# soap-disp-20210518.net
KiCad netlist of a schematic drawn in EasyEDA
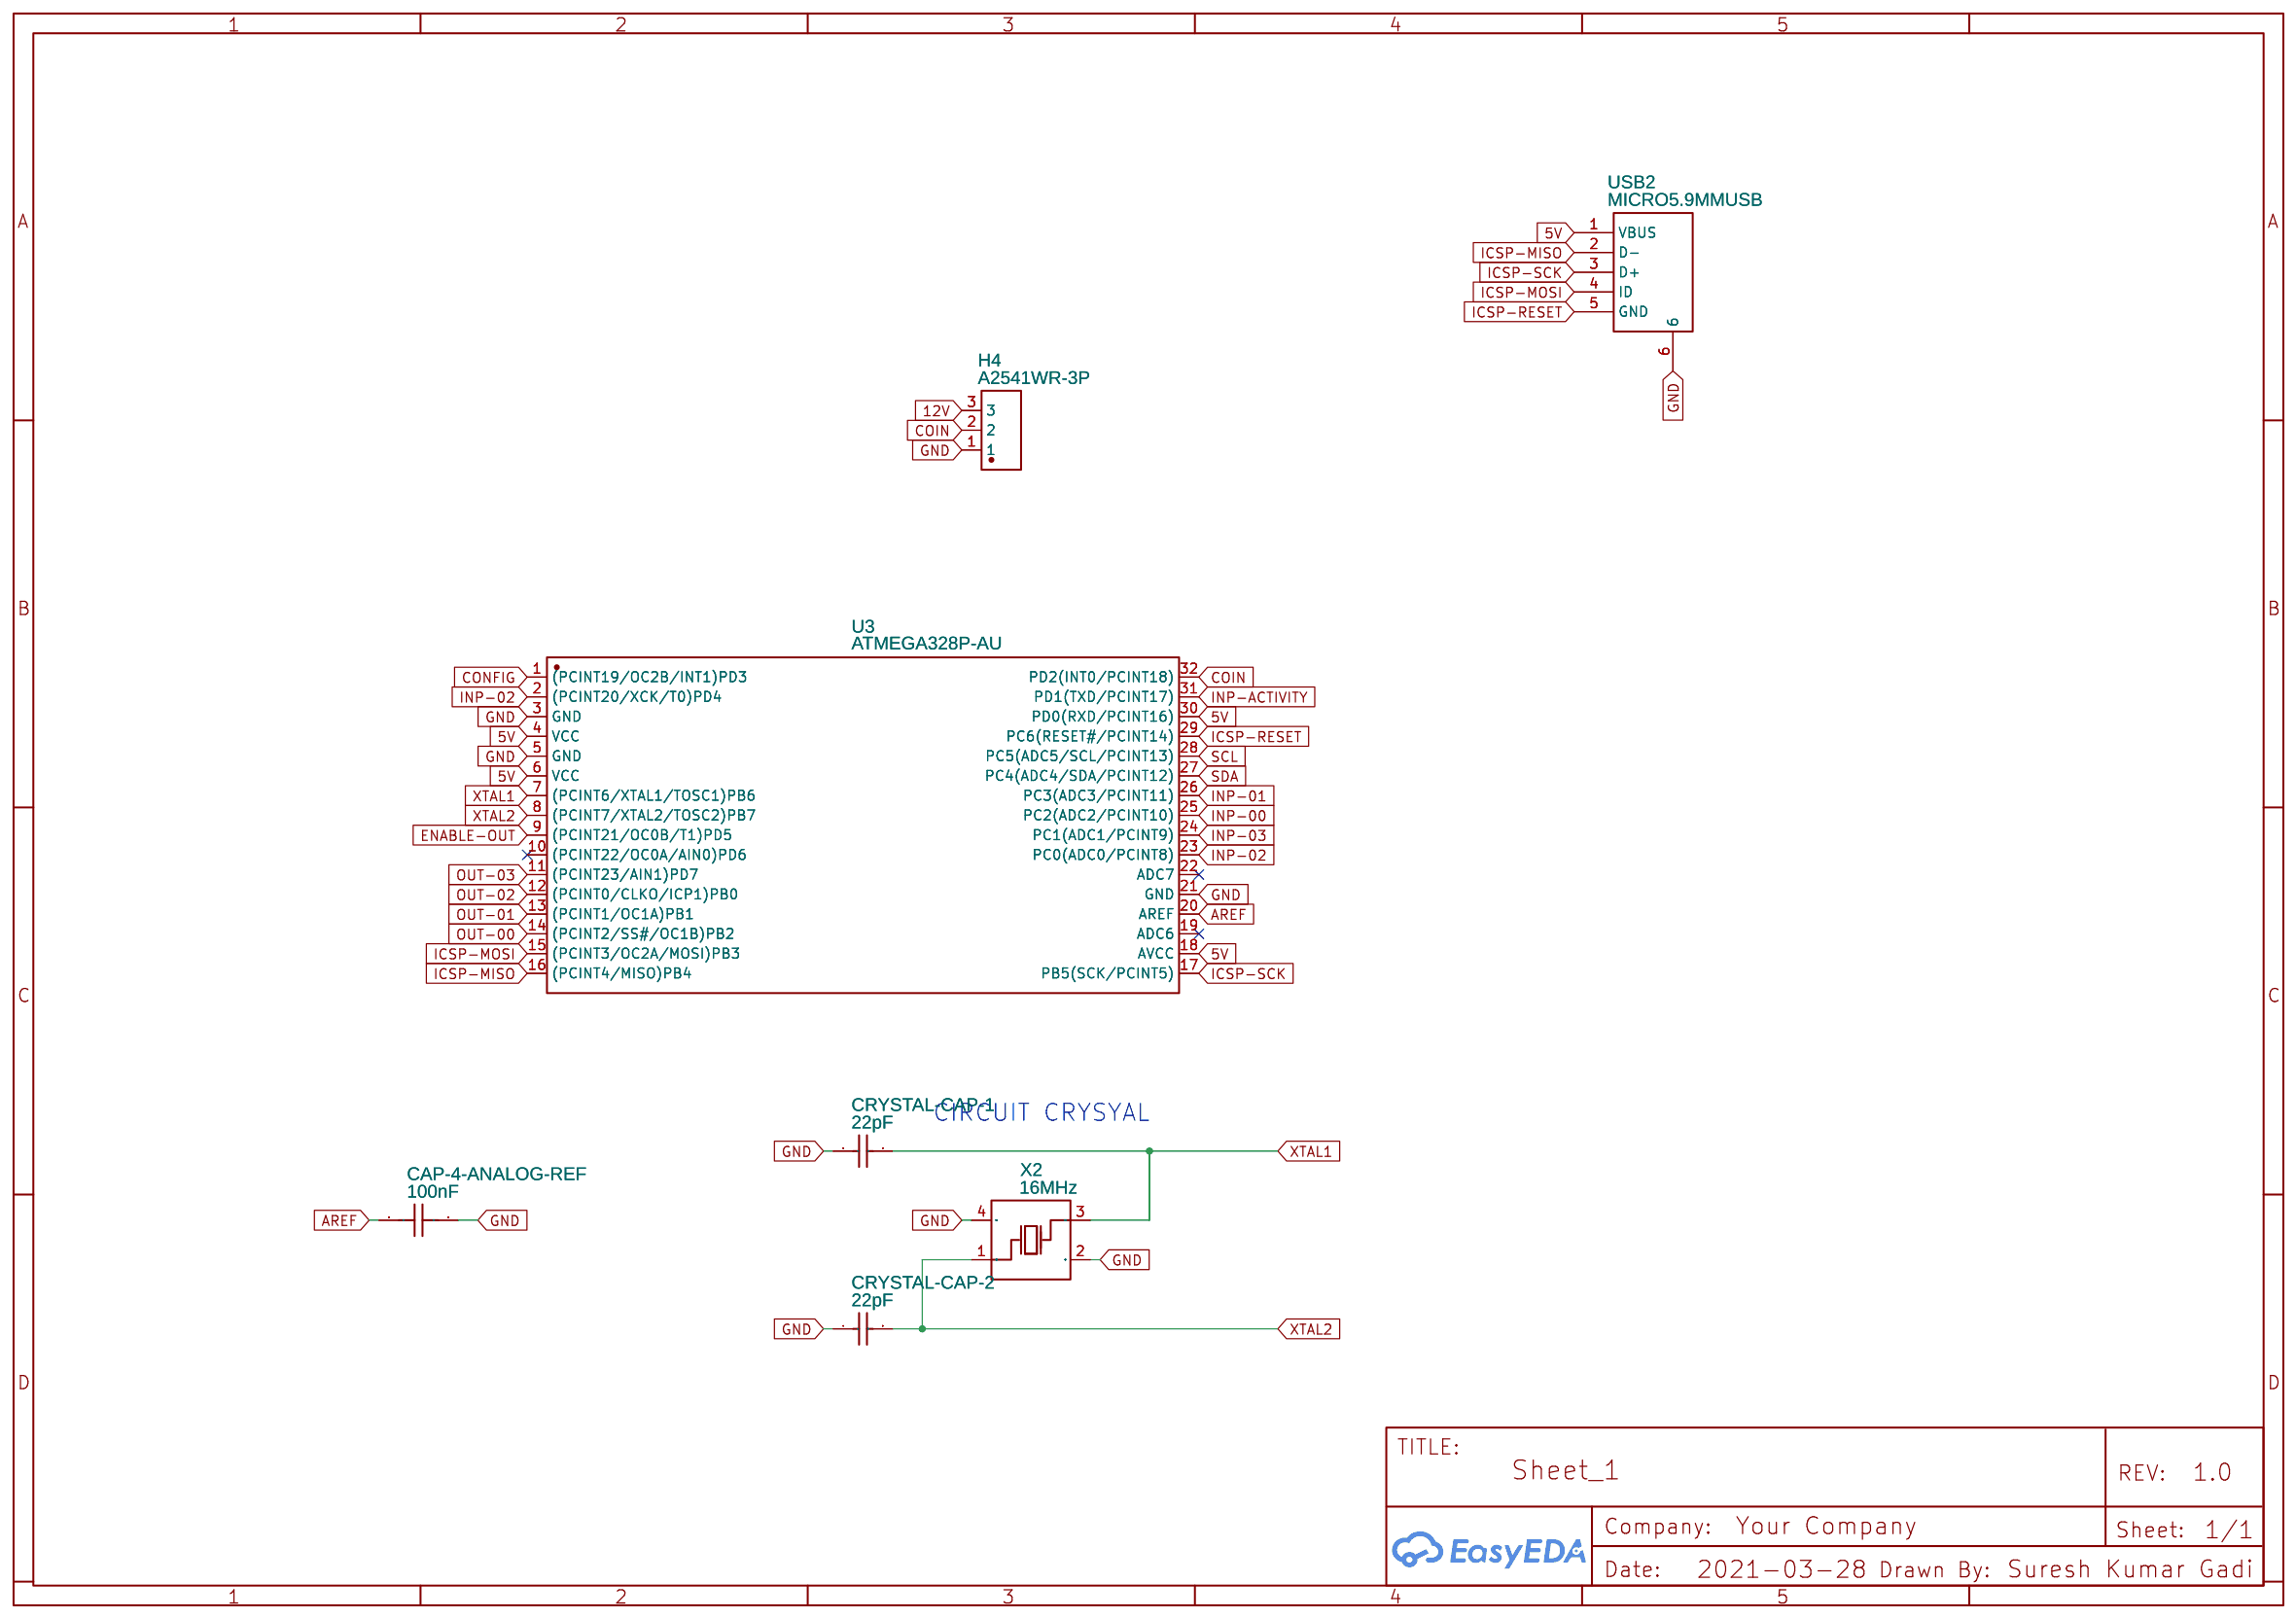
[diagram p0: Computer]
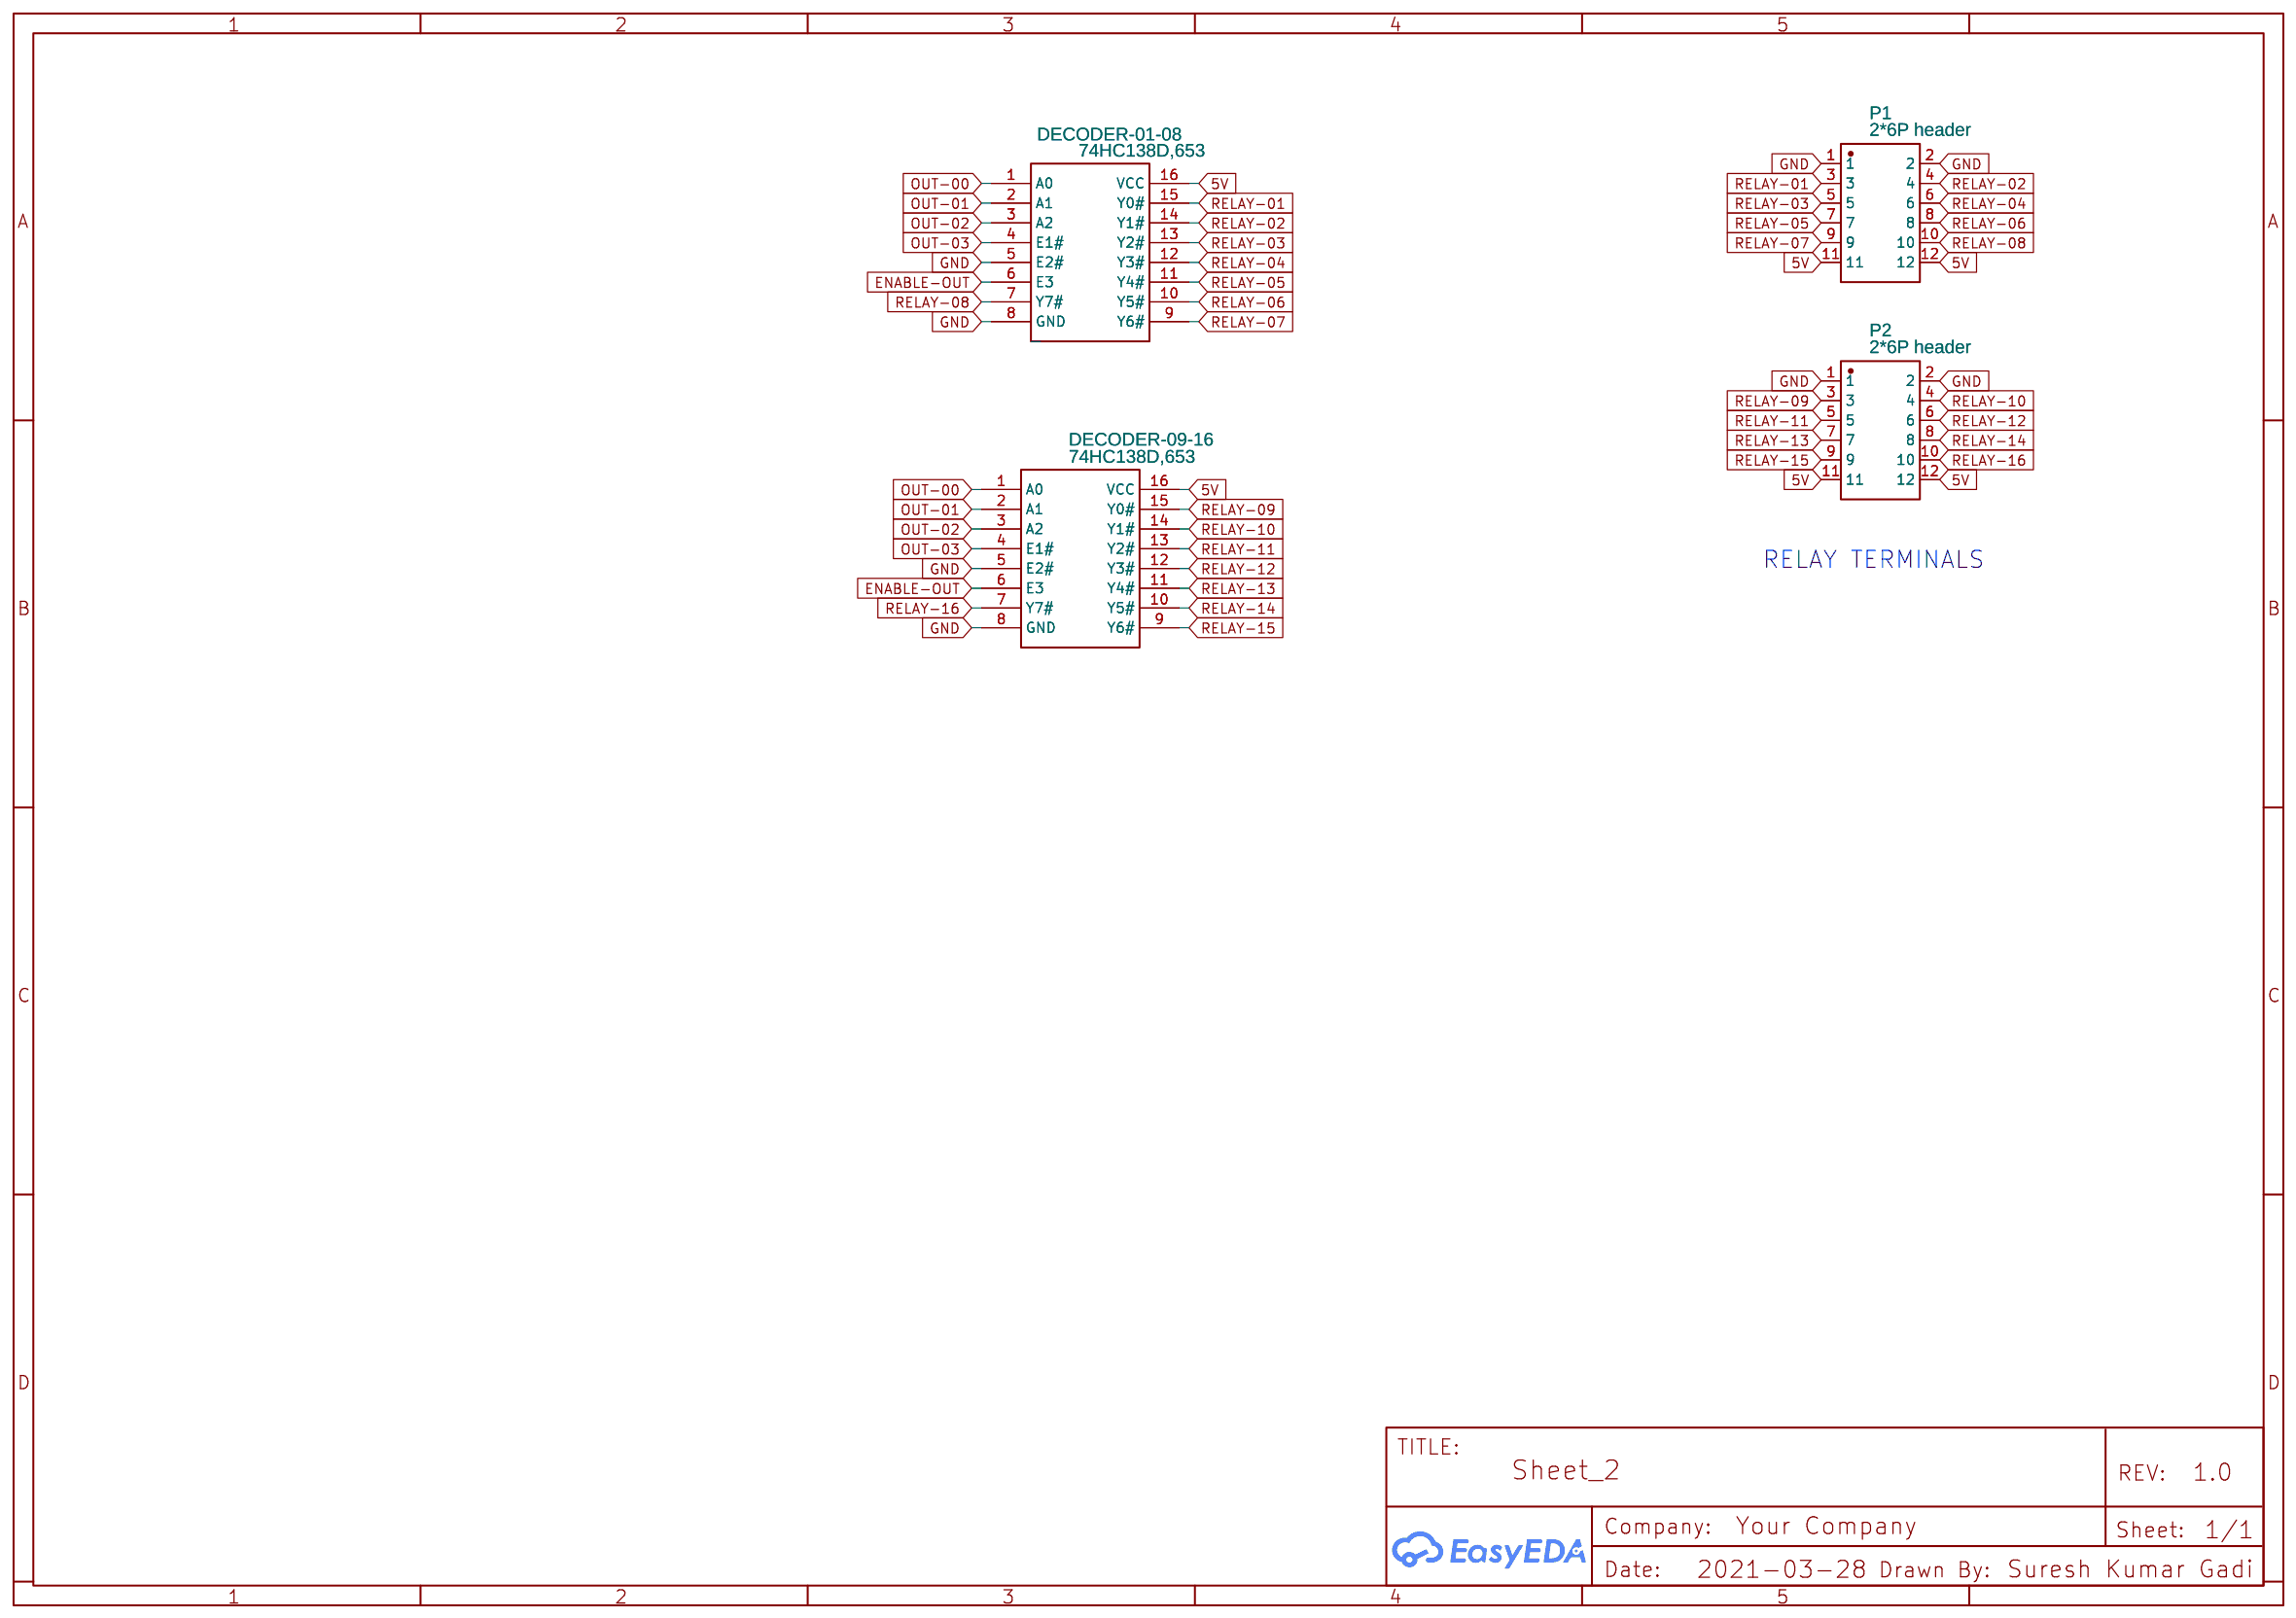
[diagram p1: Relays]
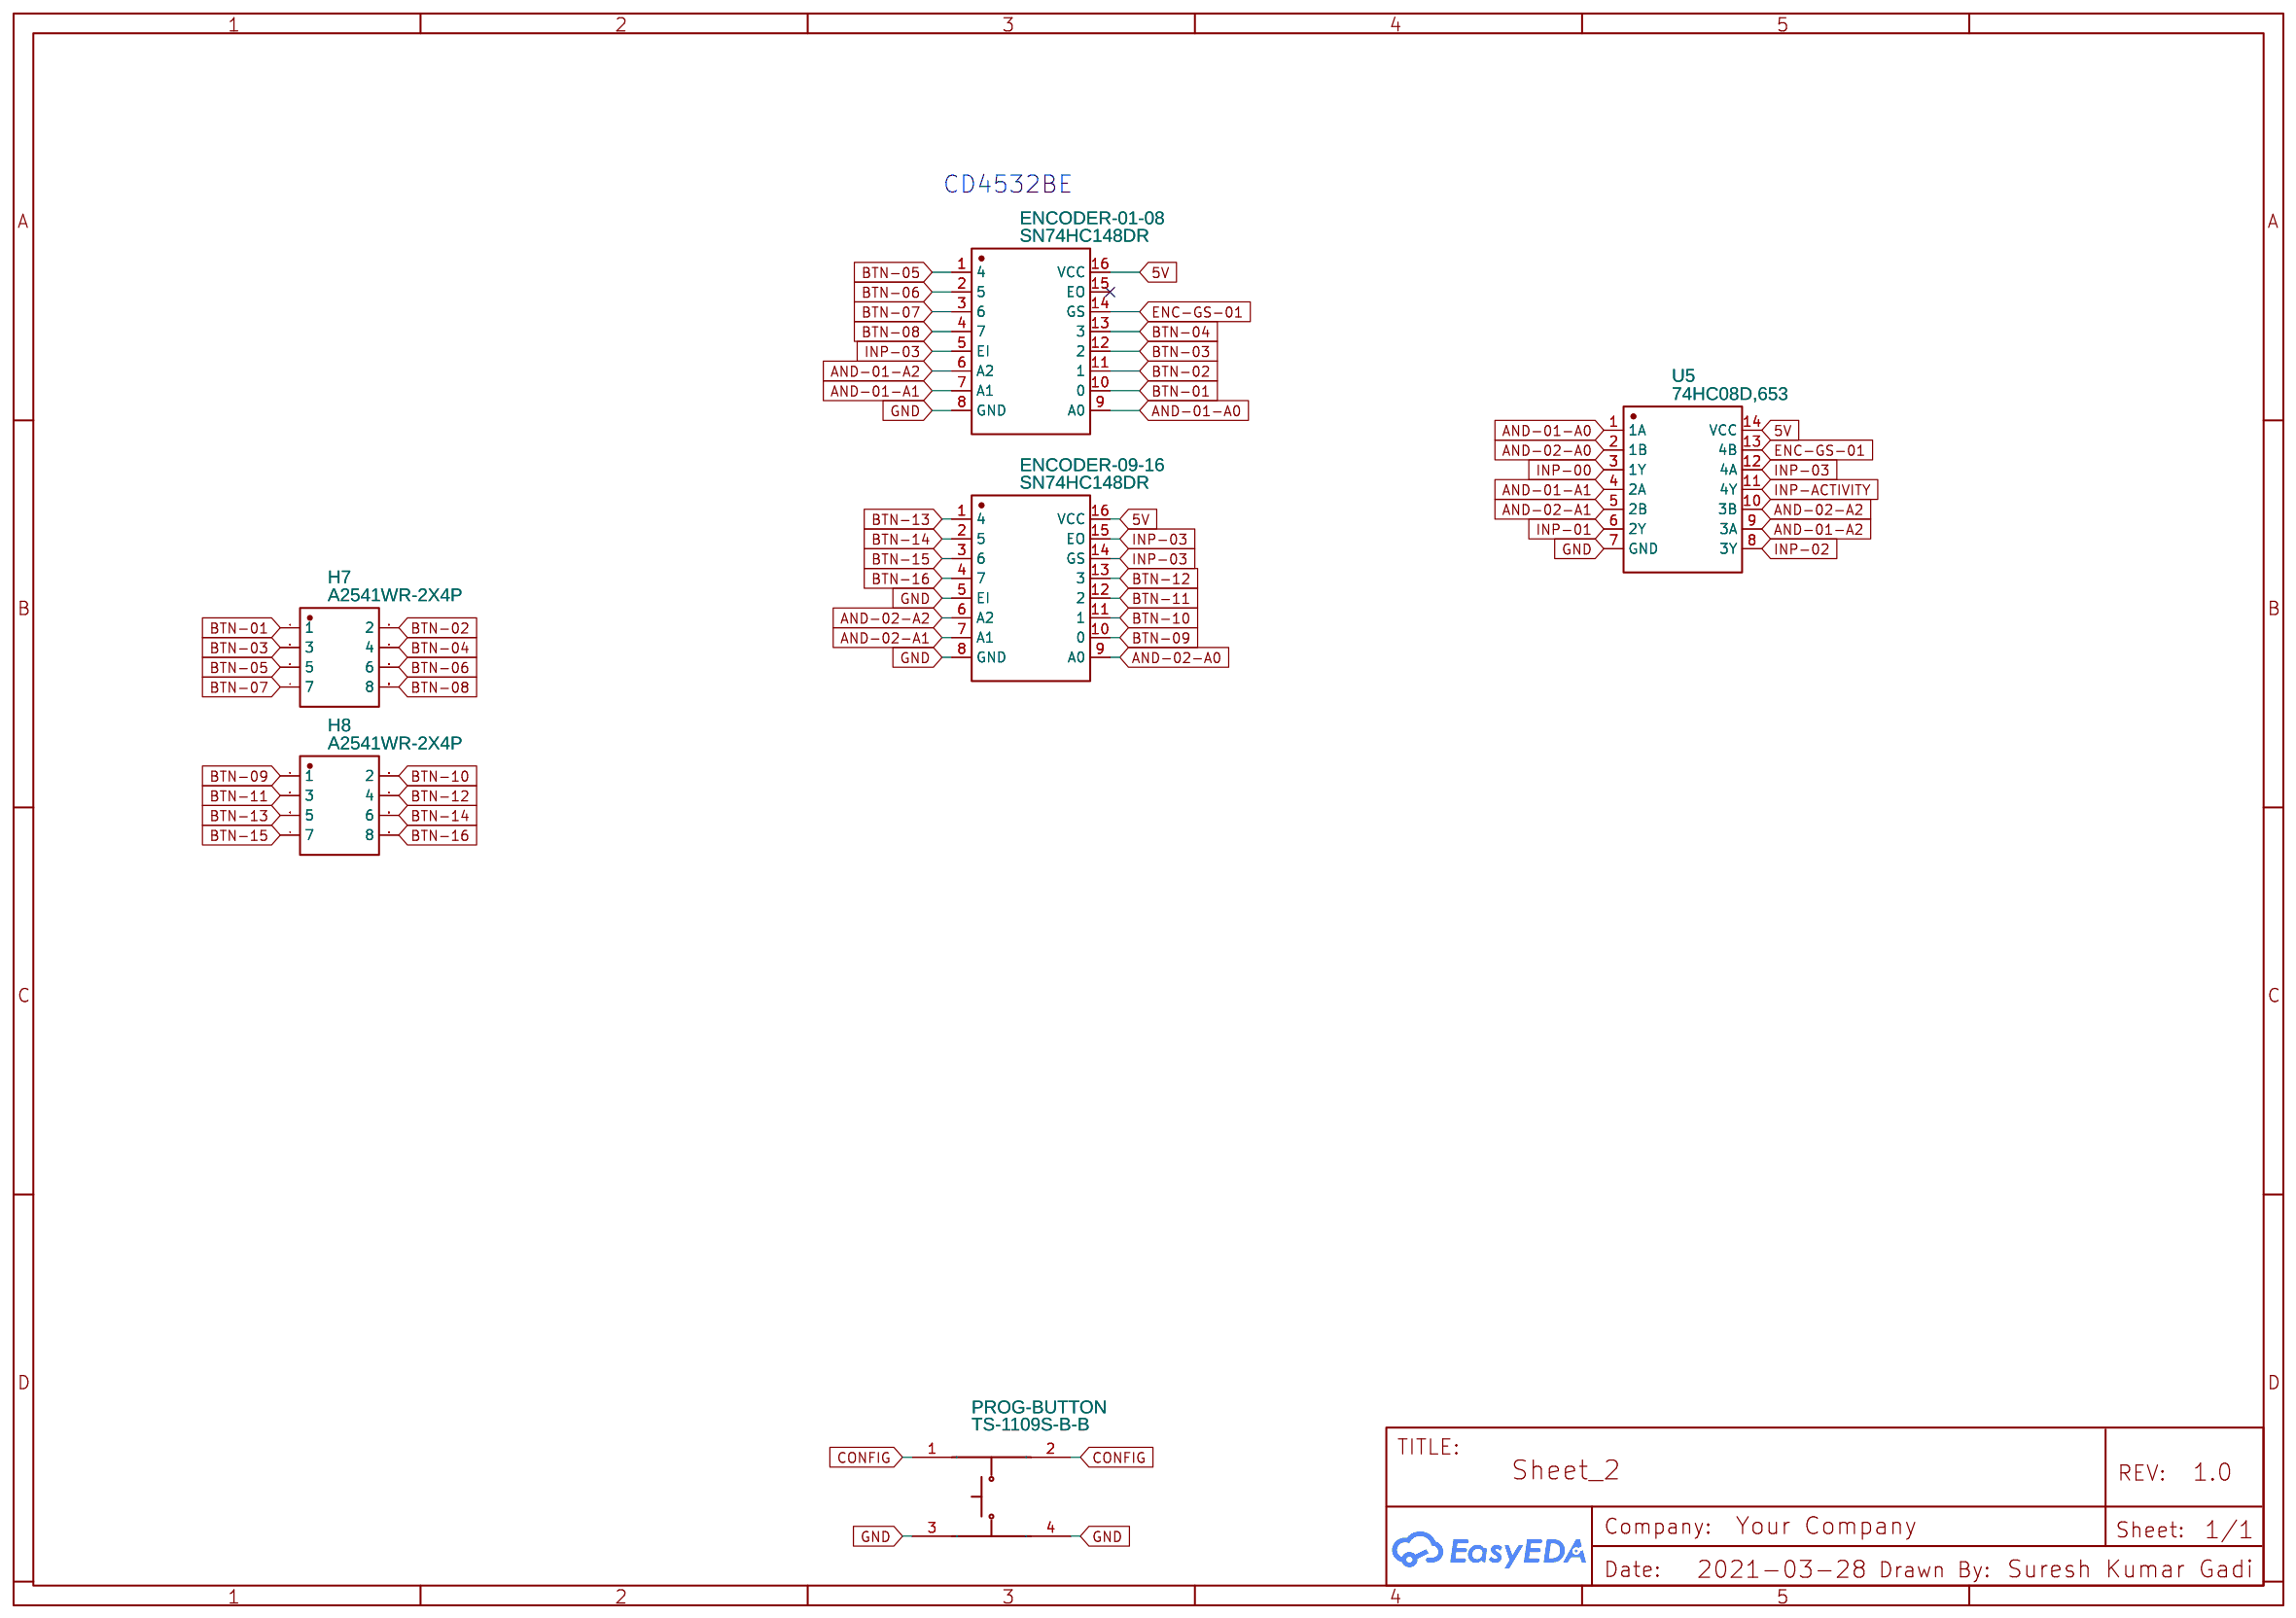
[diagram p2: Buttons]
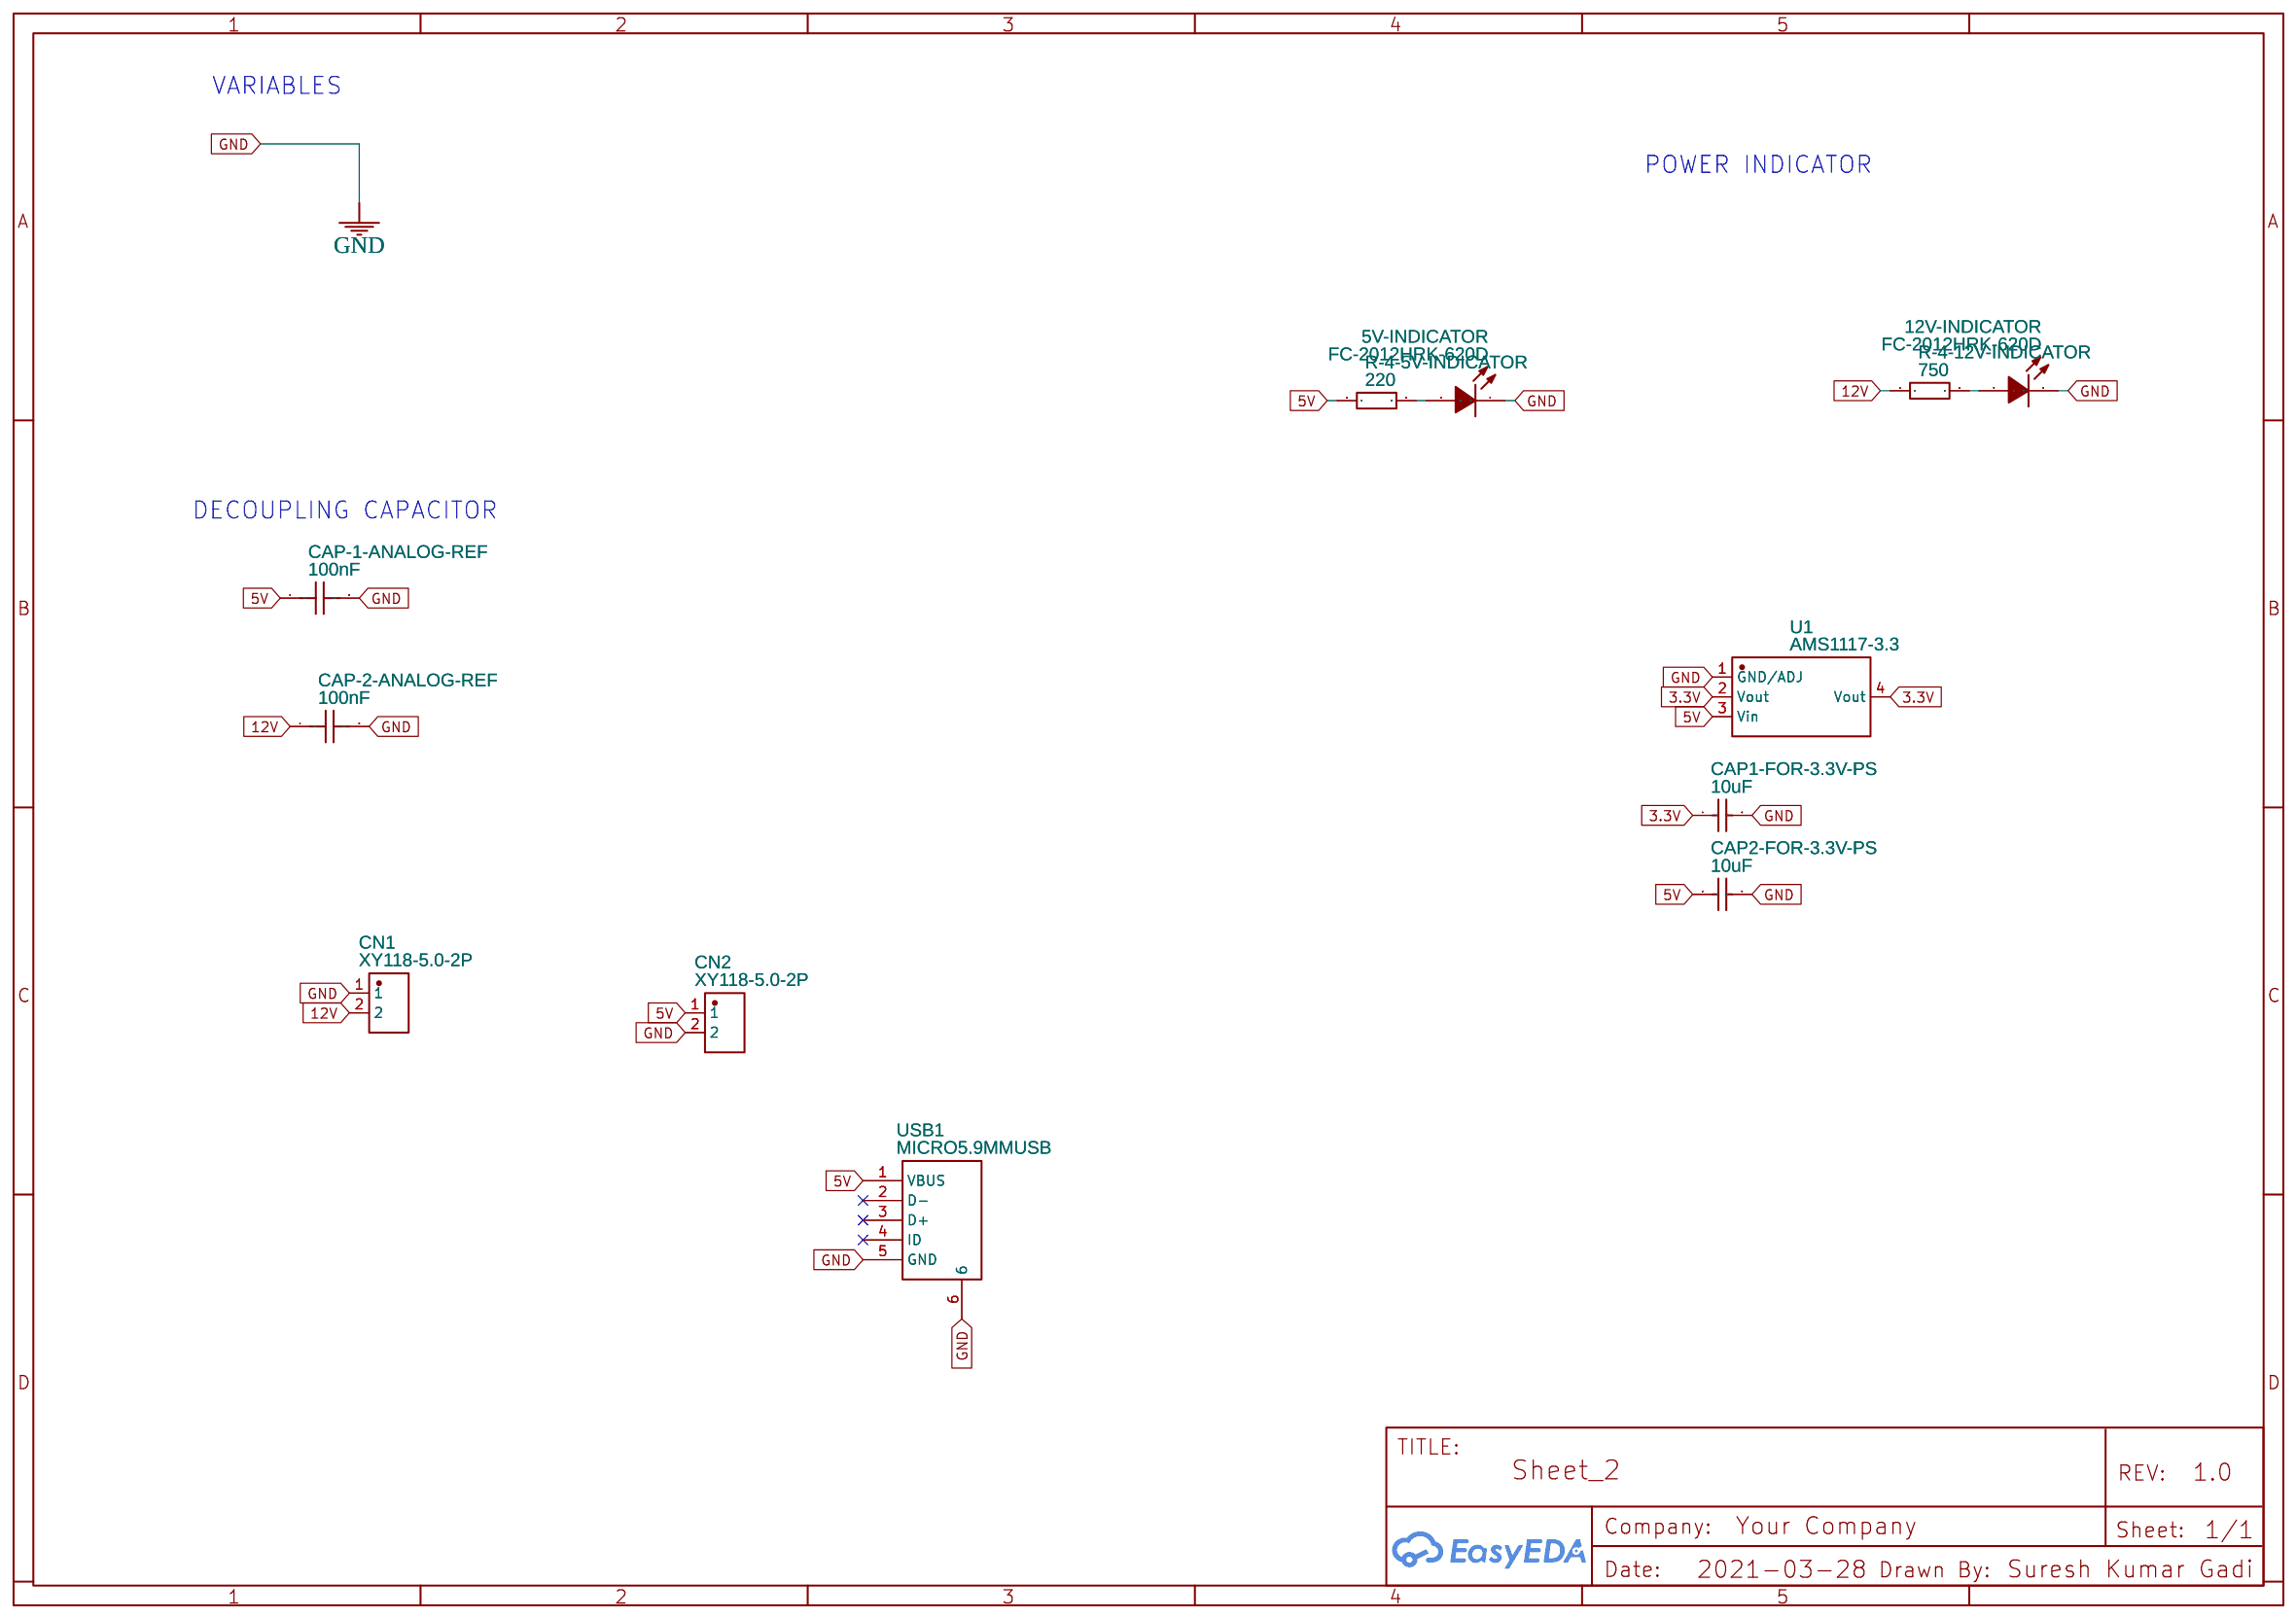
[diagram p3: Power]
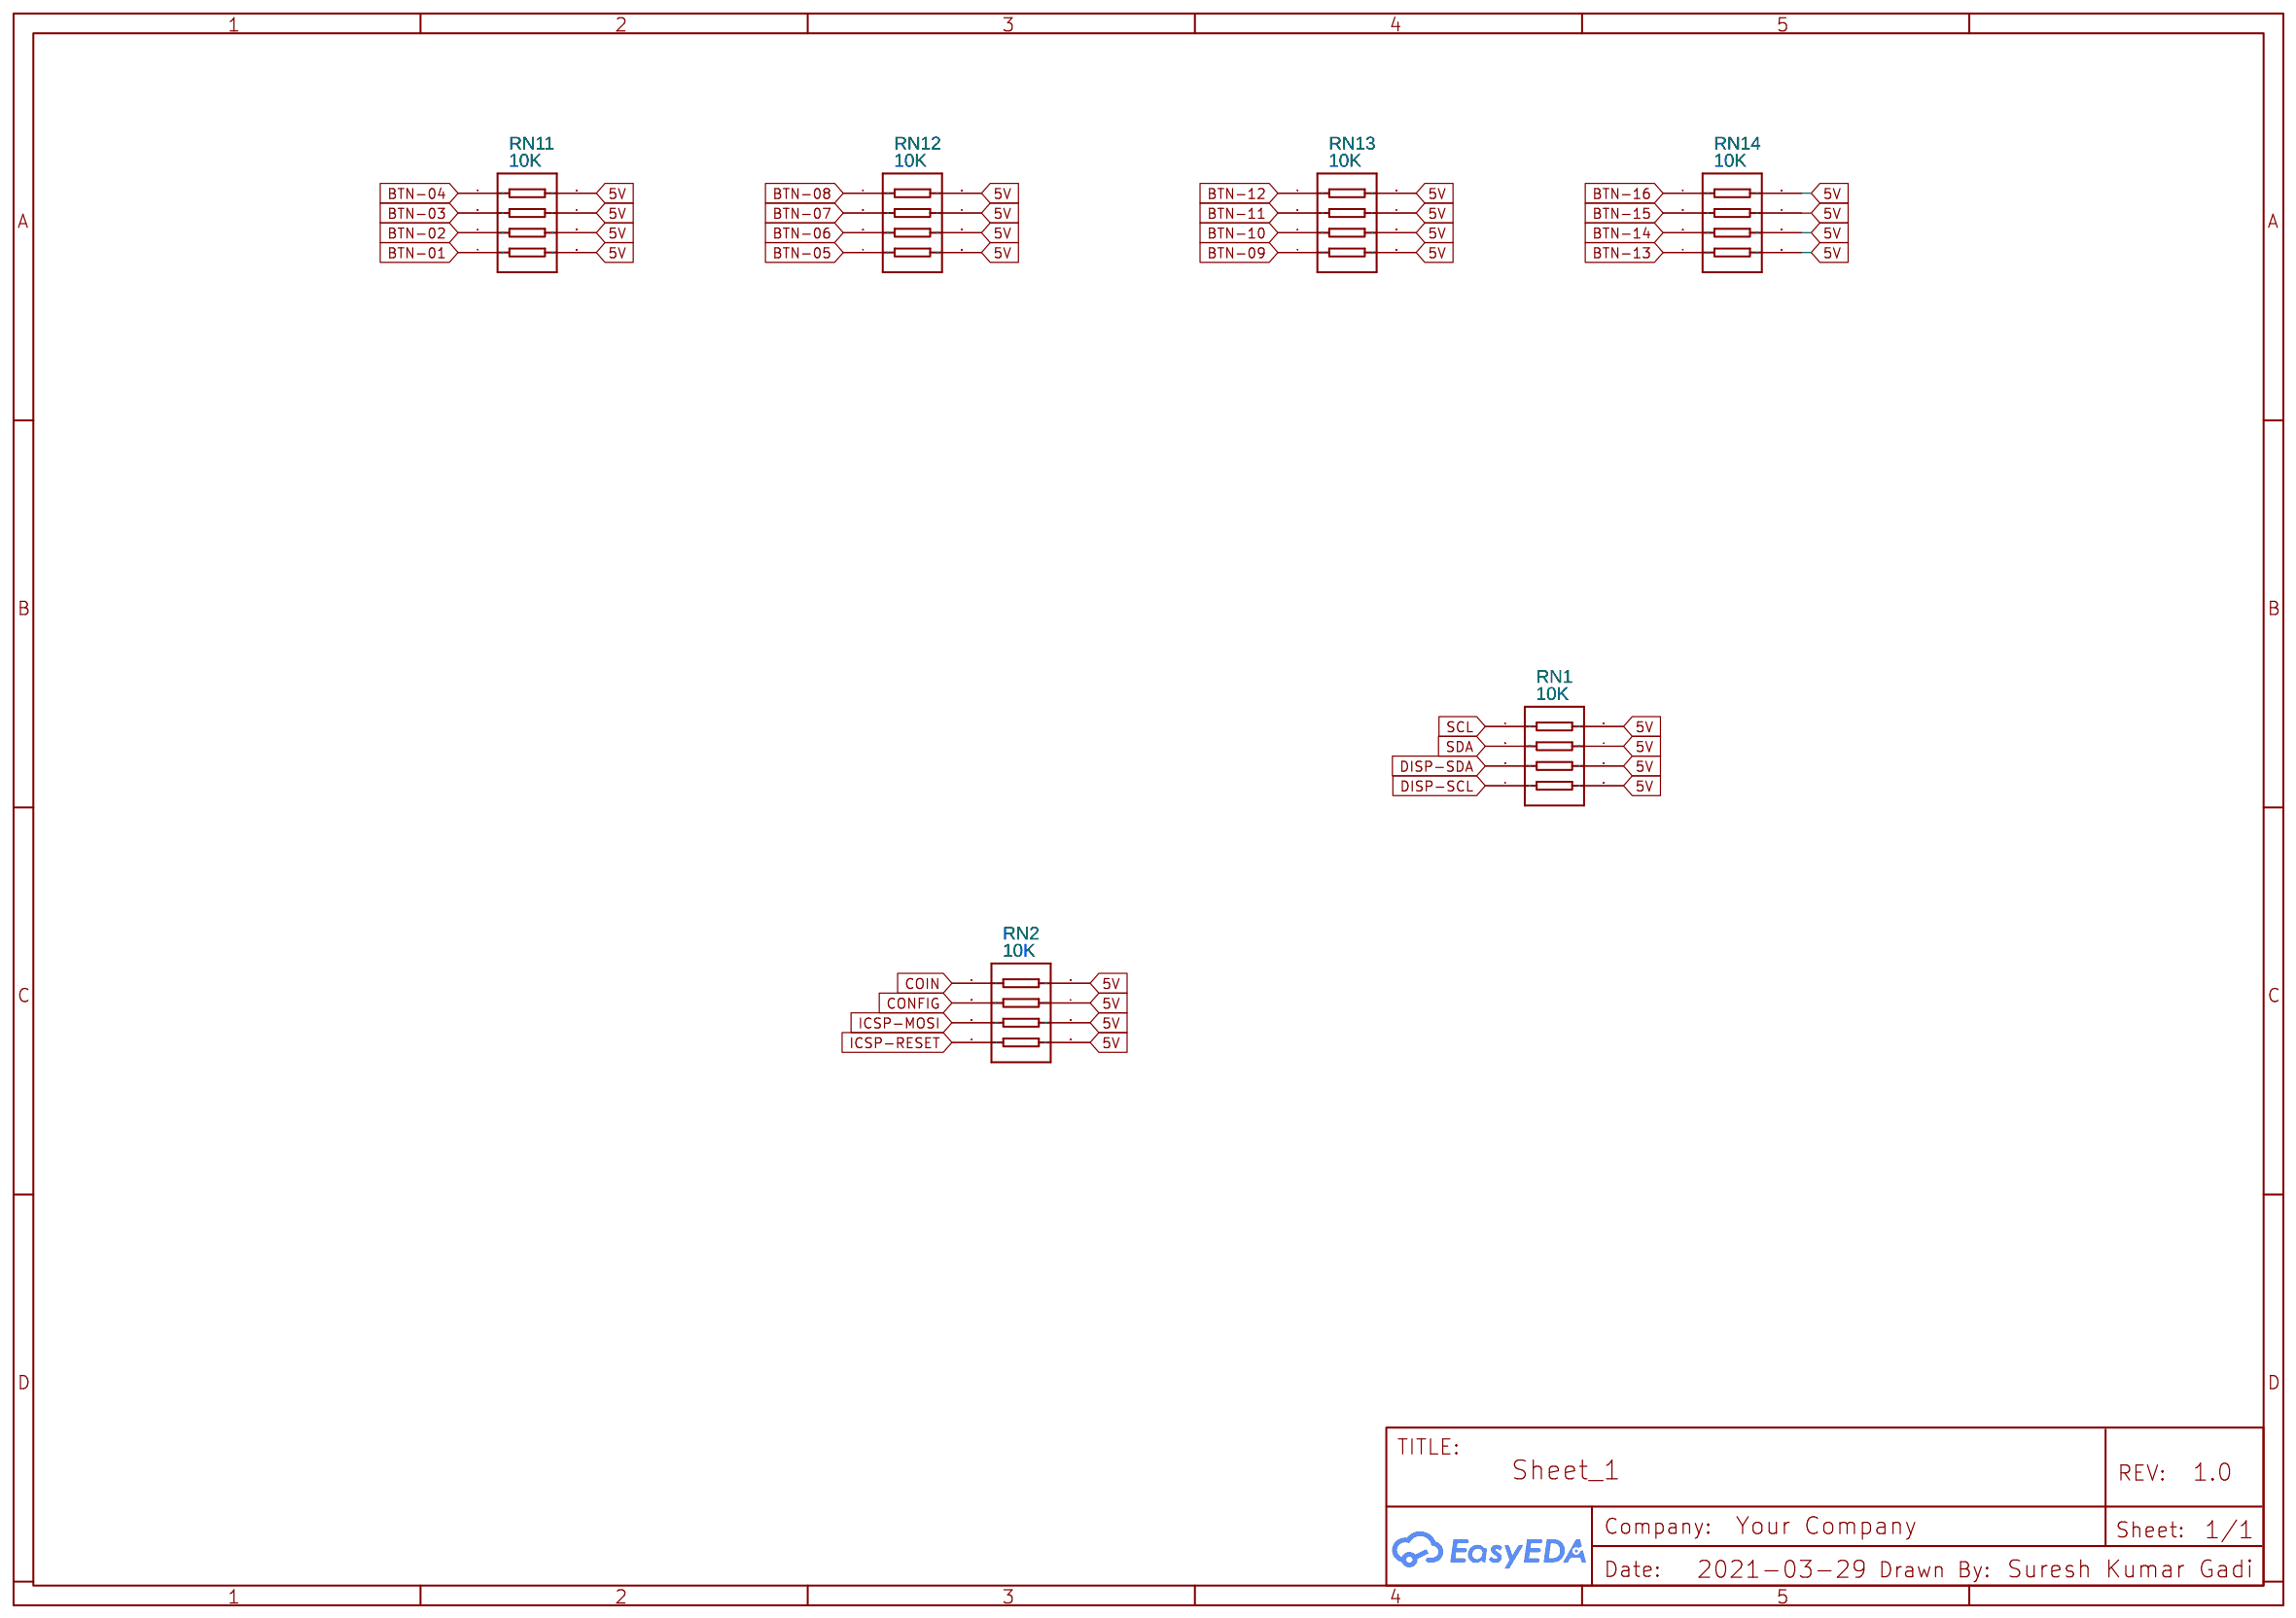
[diagram p4: Pull up-down]
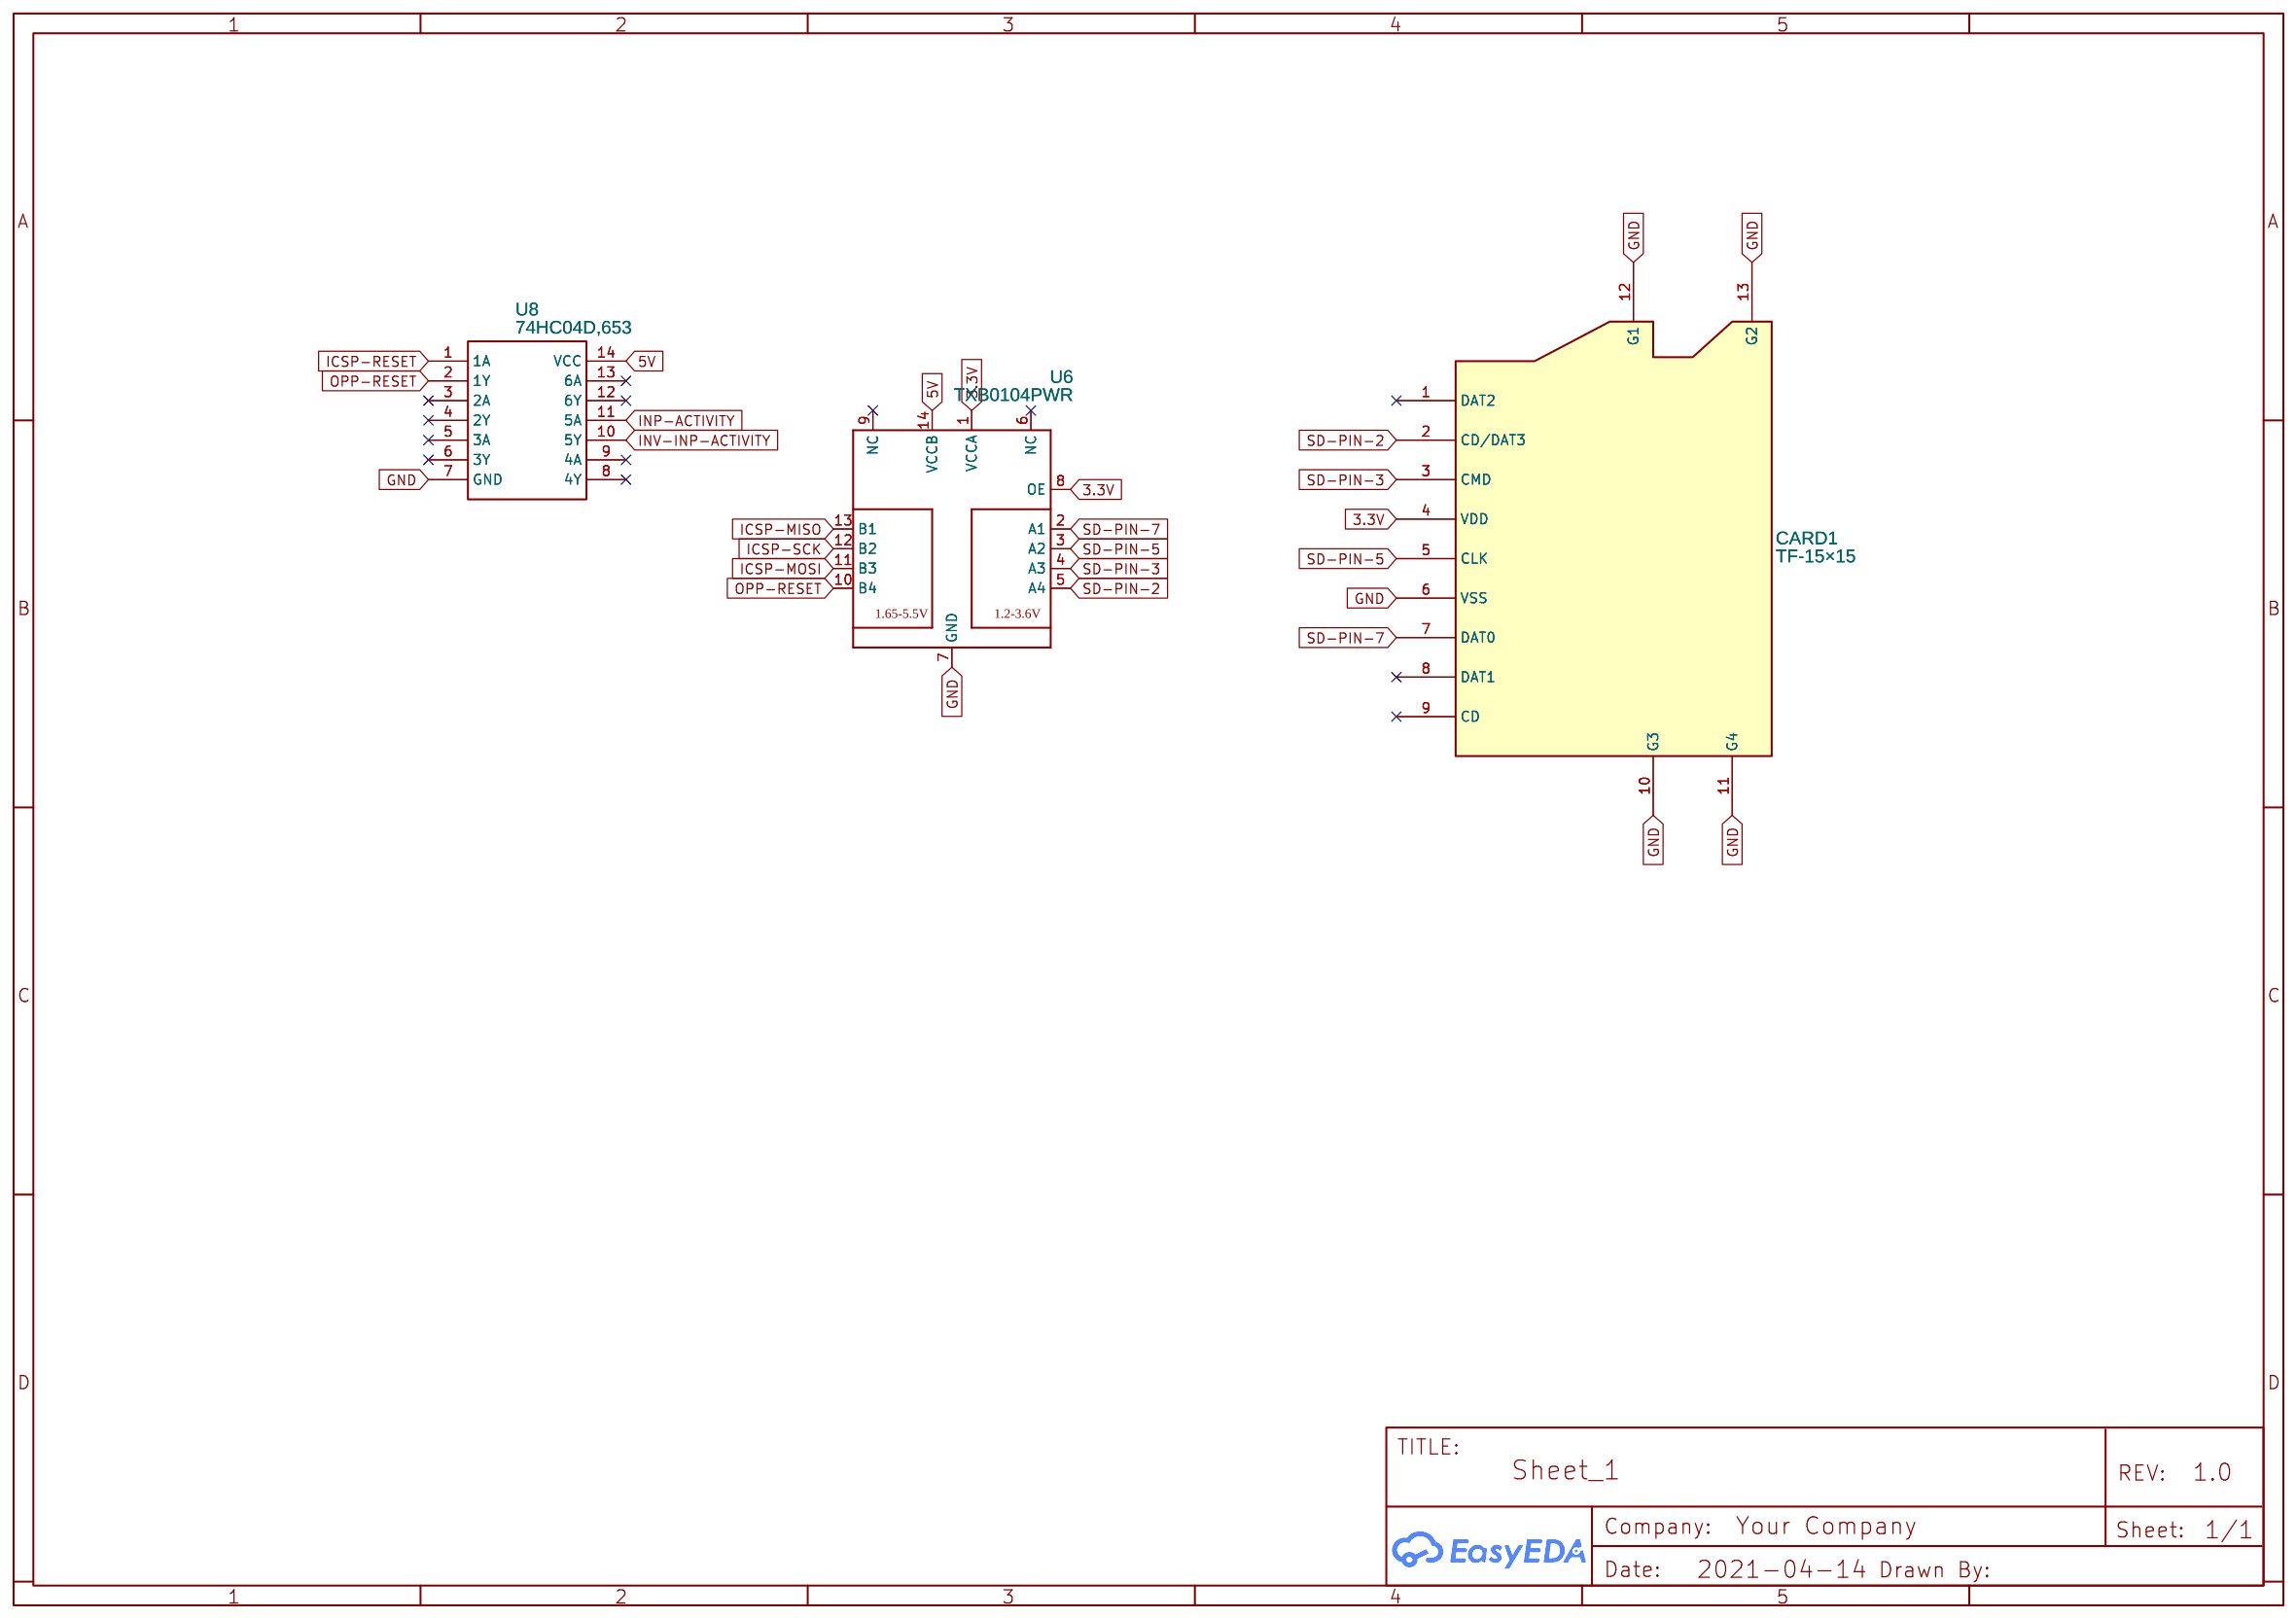
[diagram p5: SD Card]
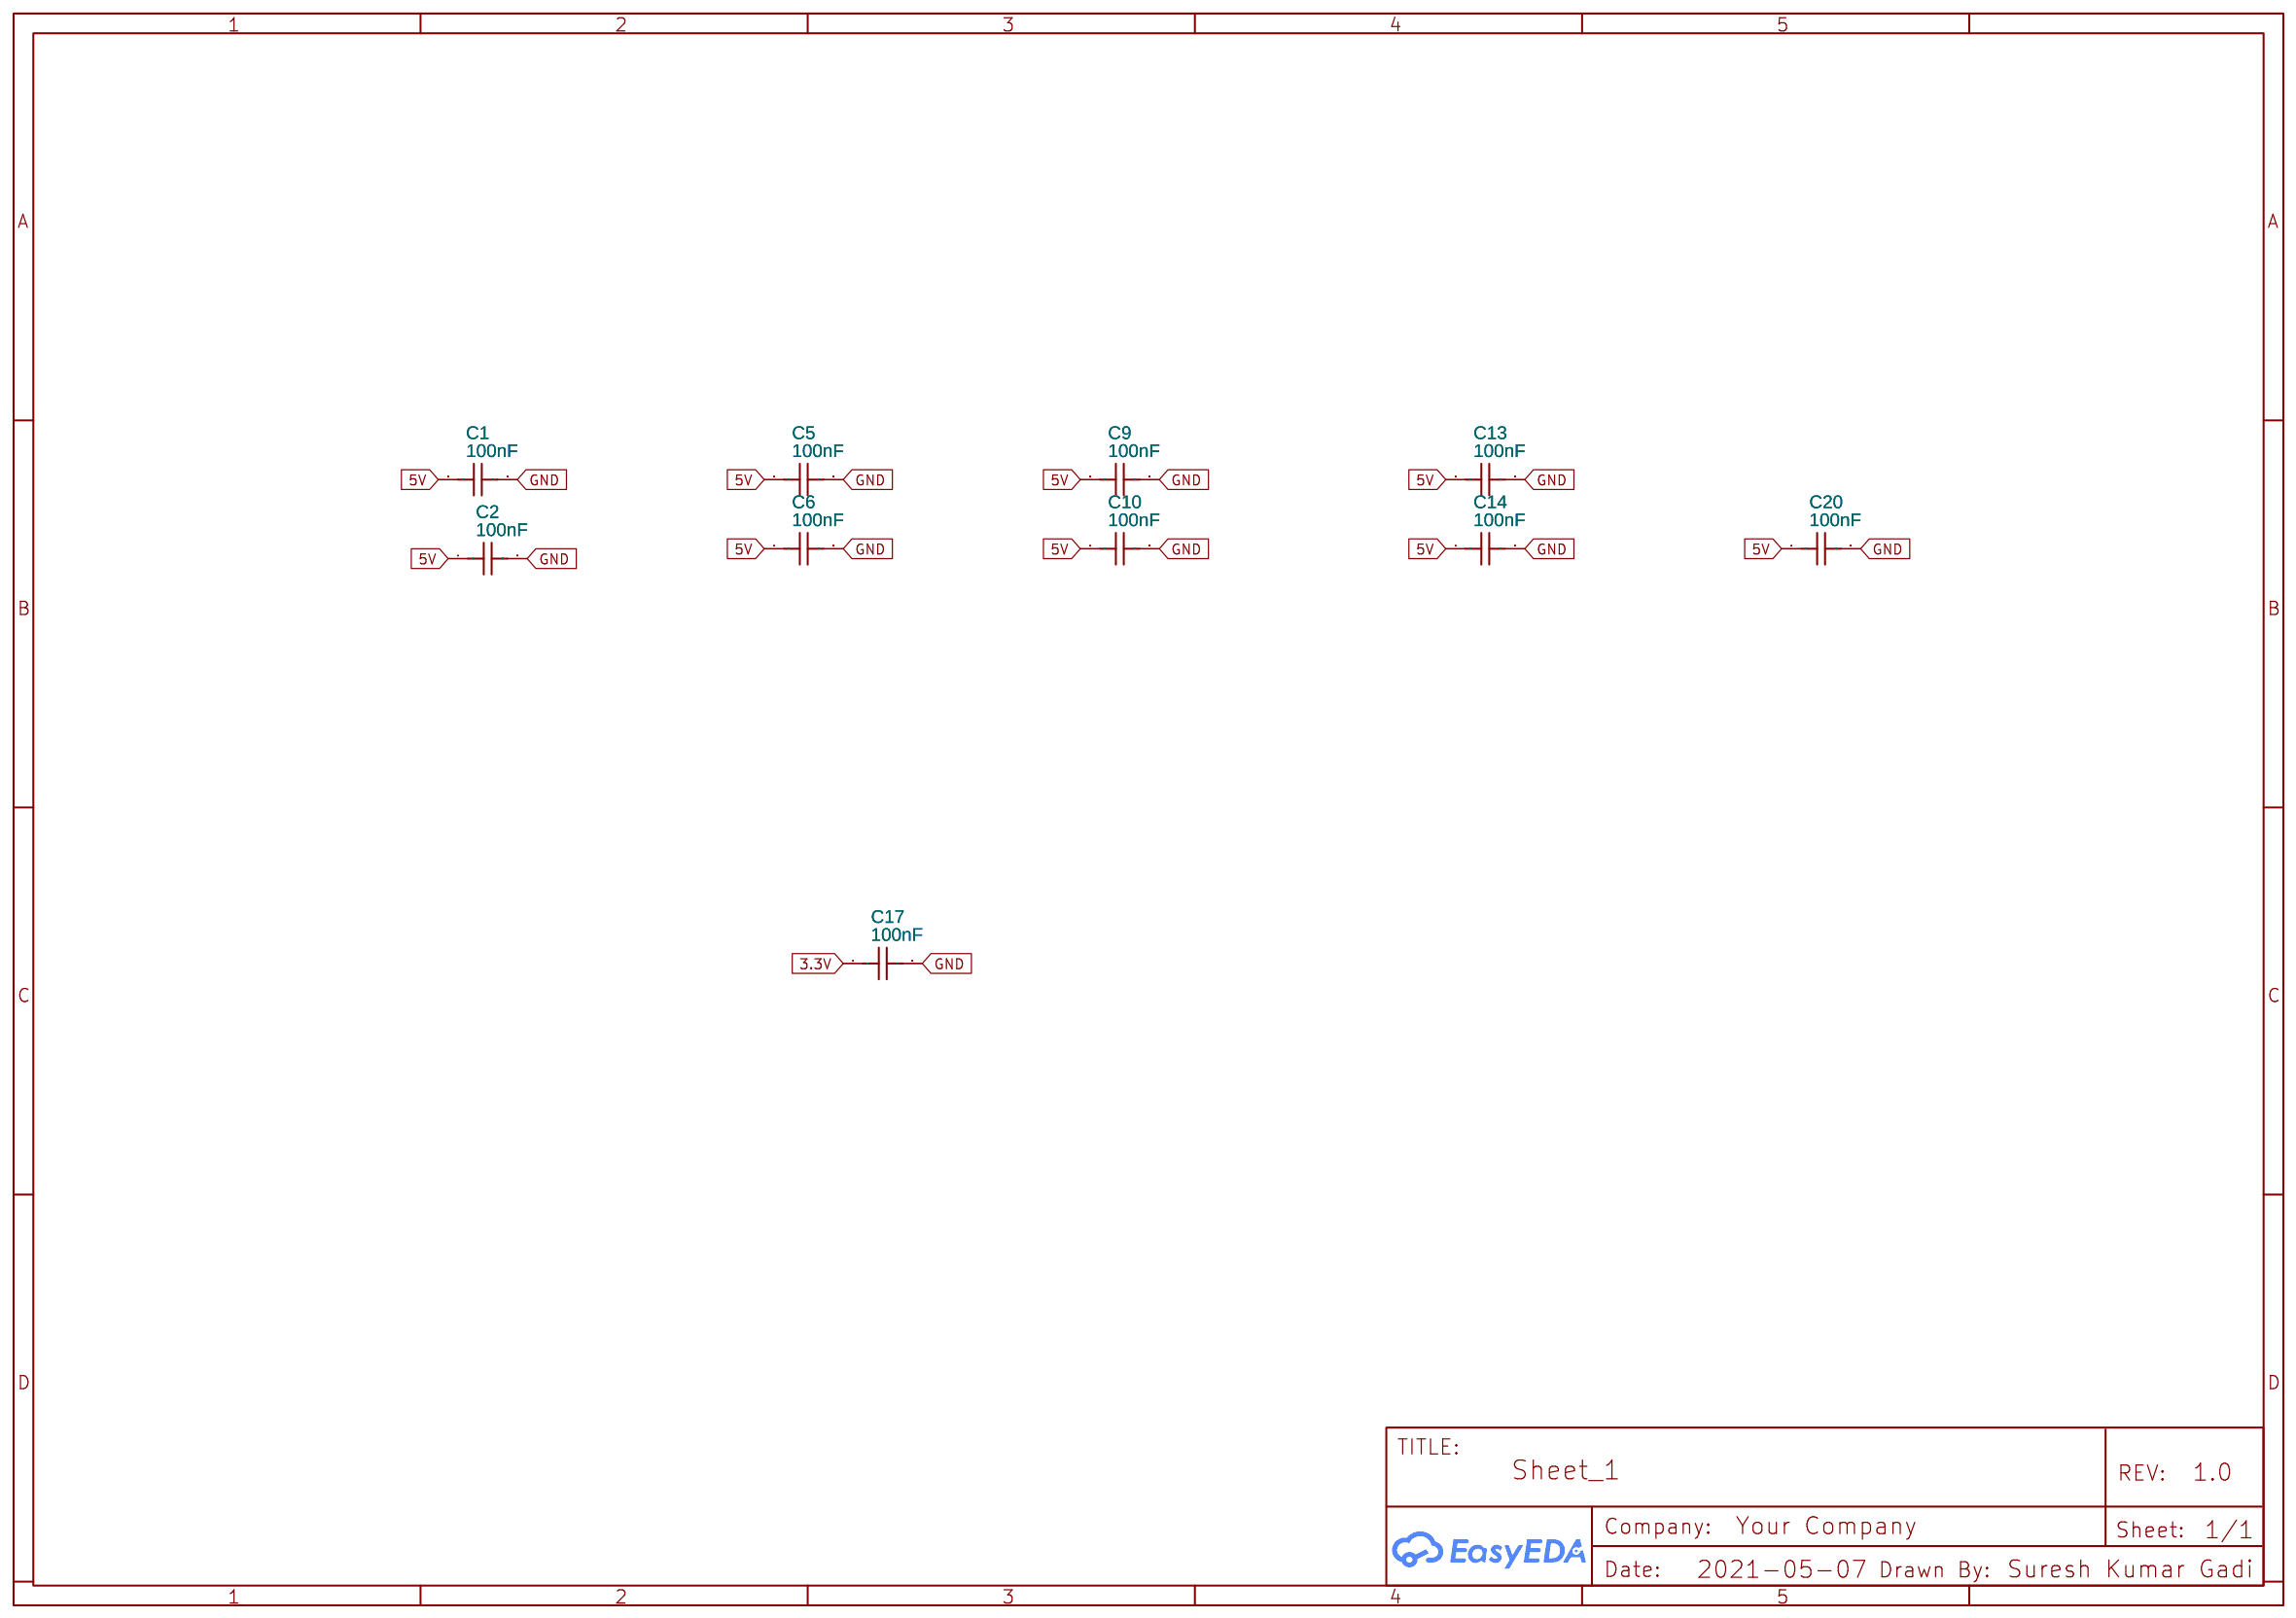
[diagram p6: Capacitor]
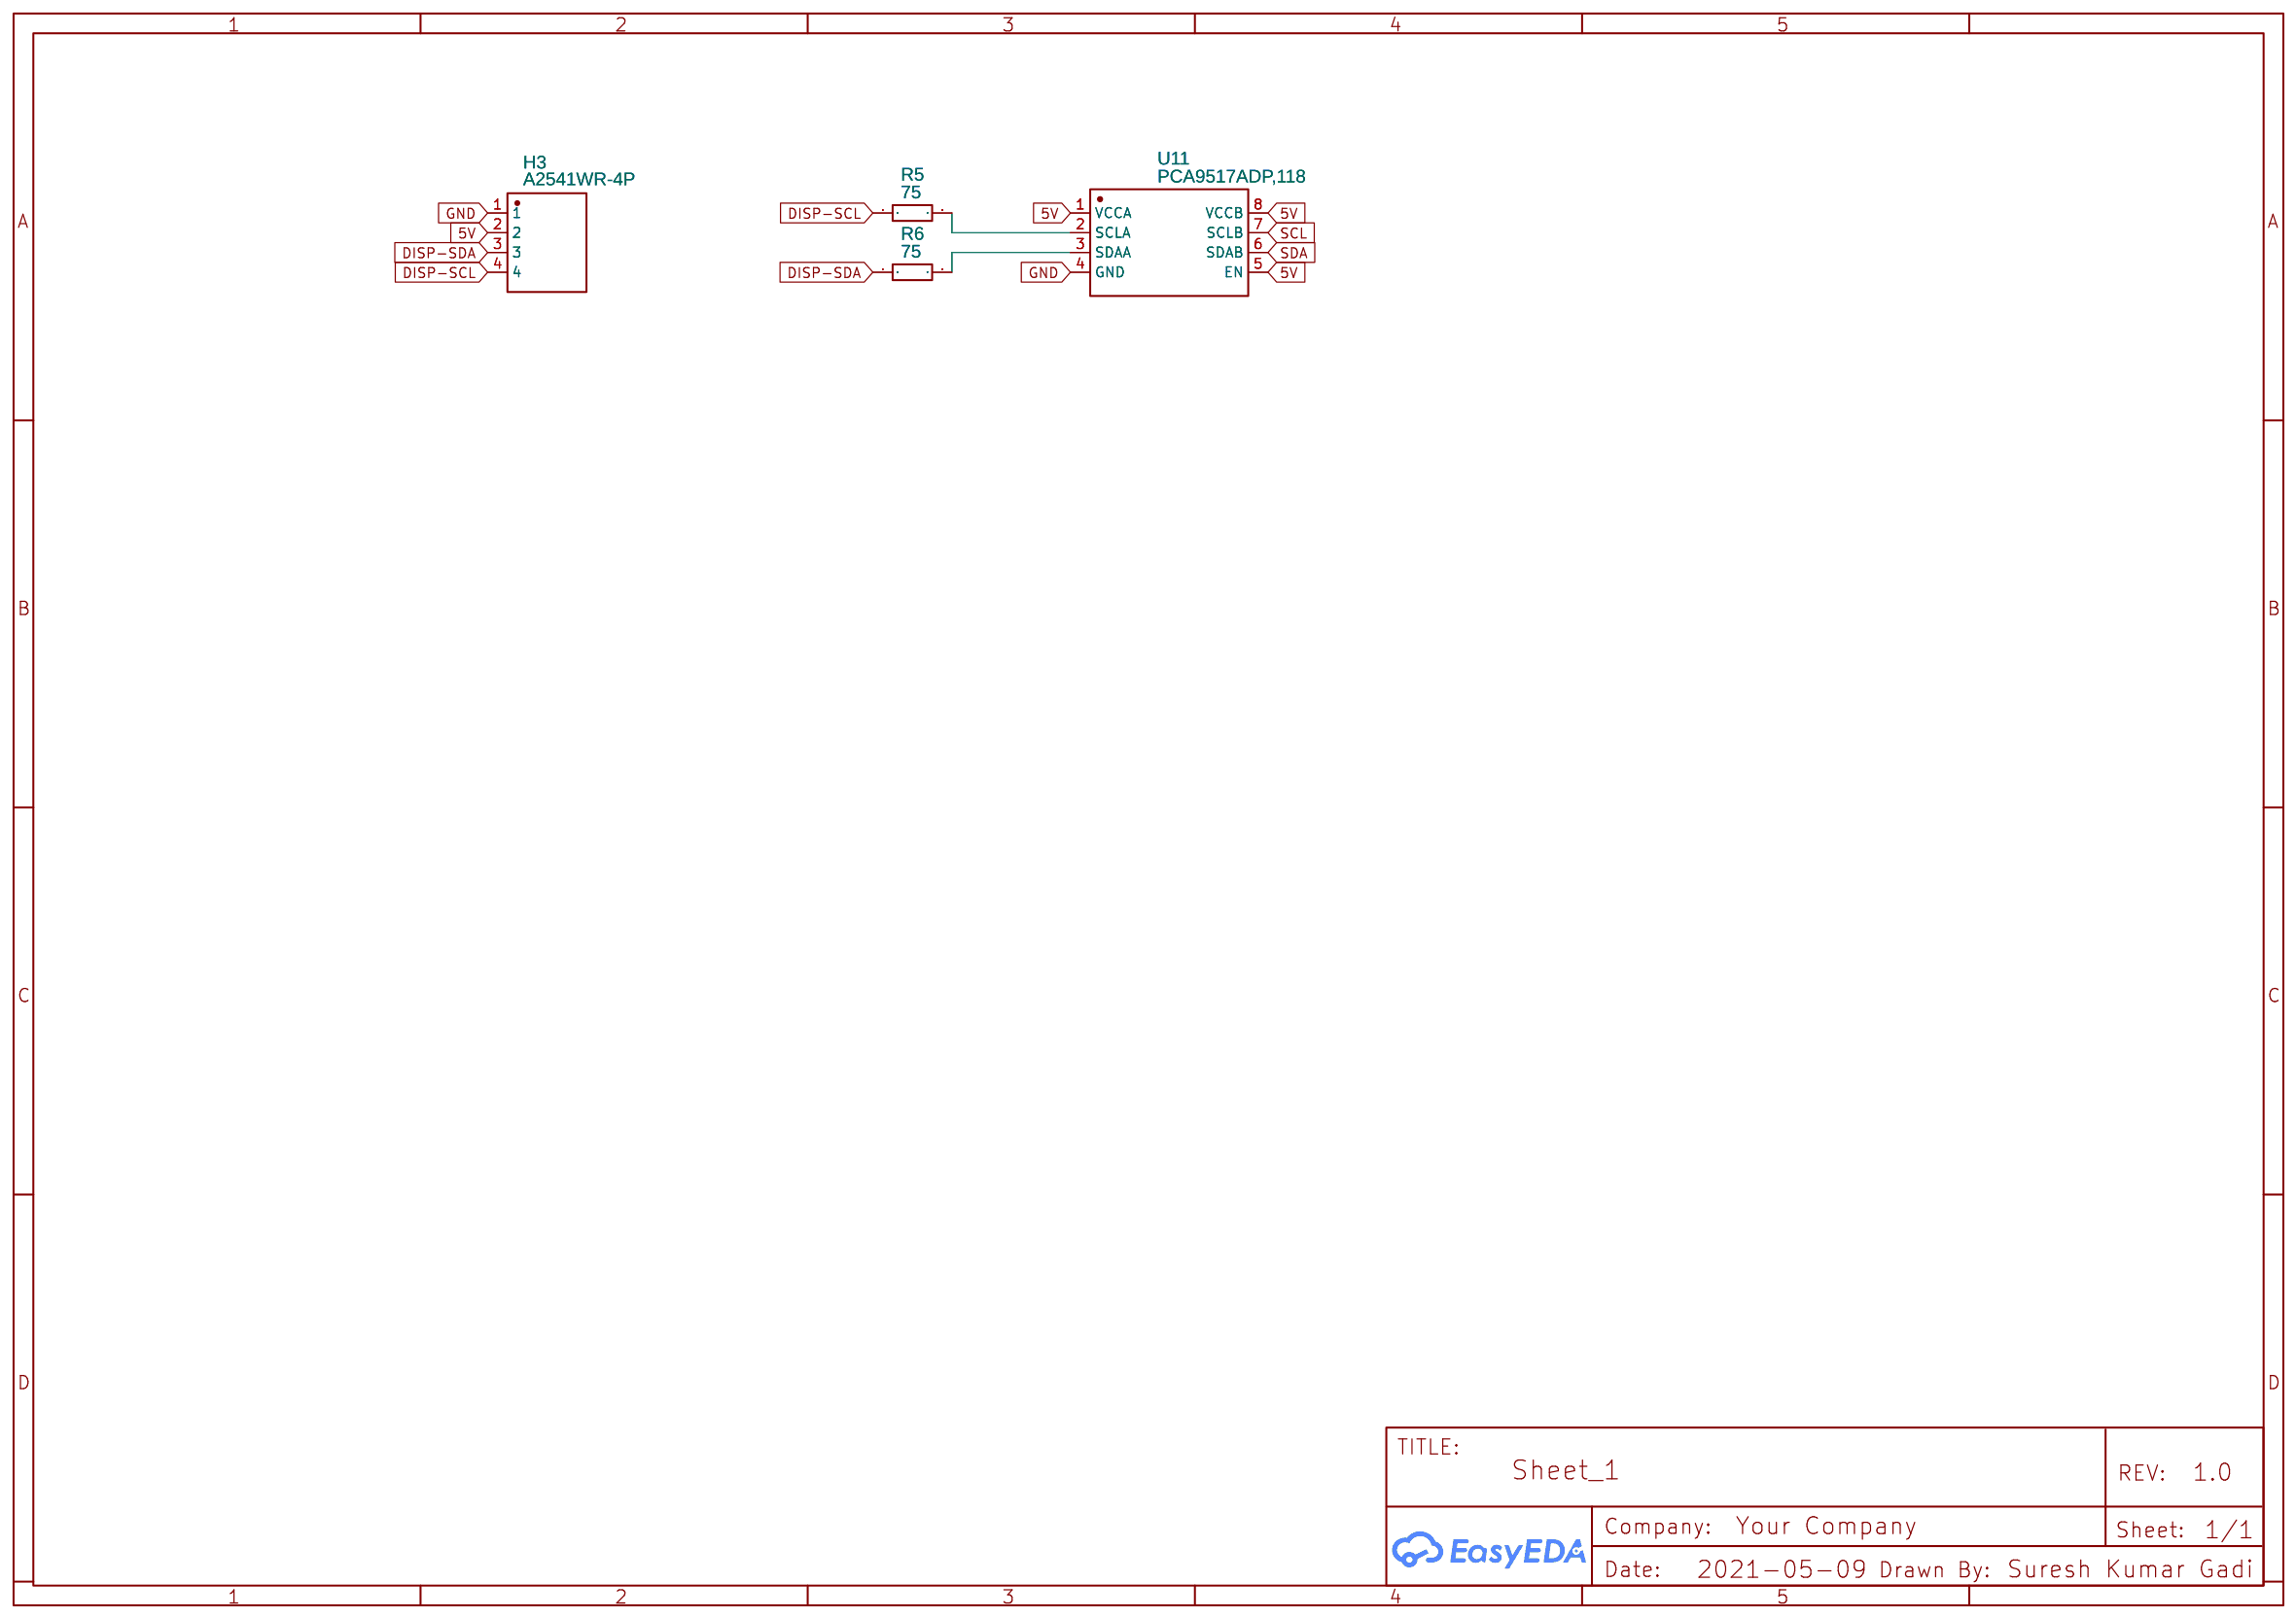
[diagram p7: Display]
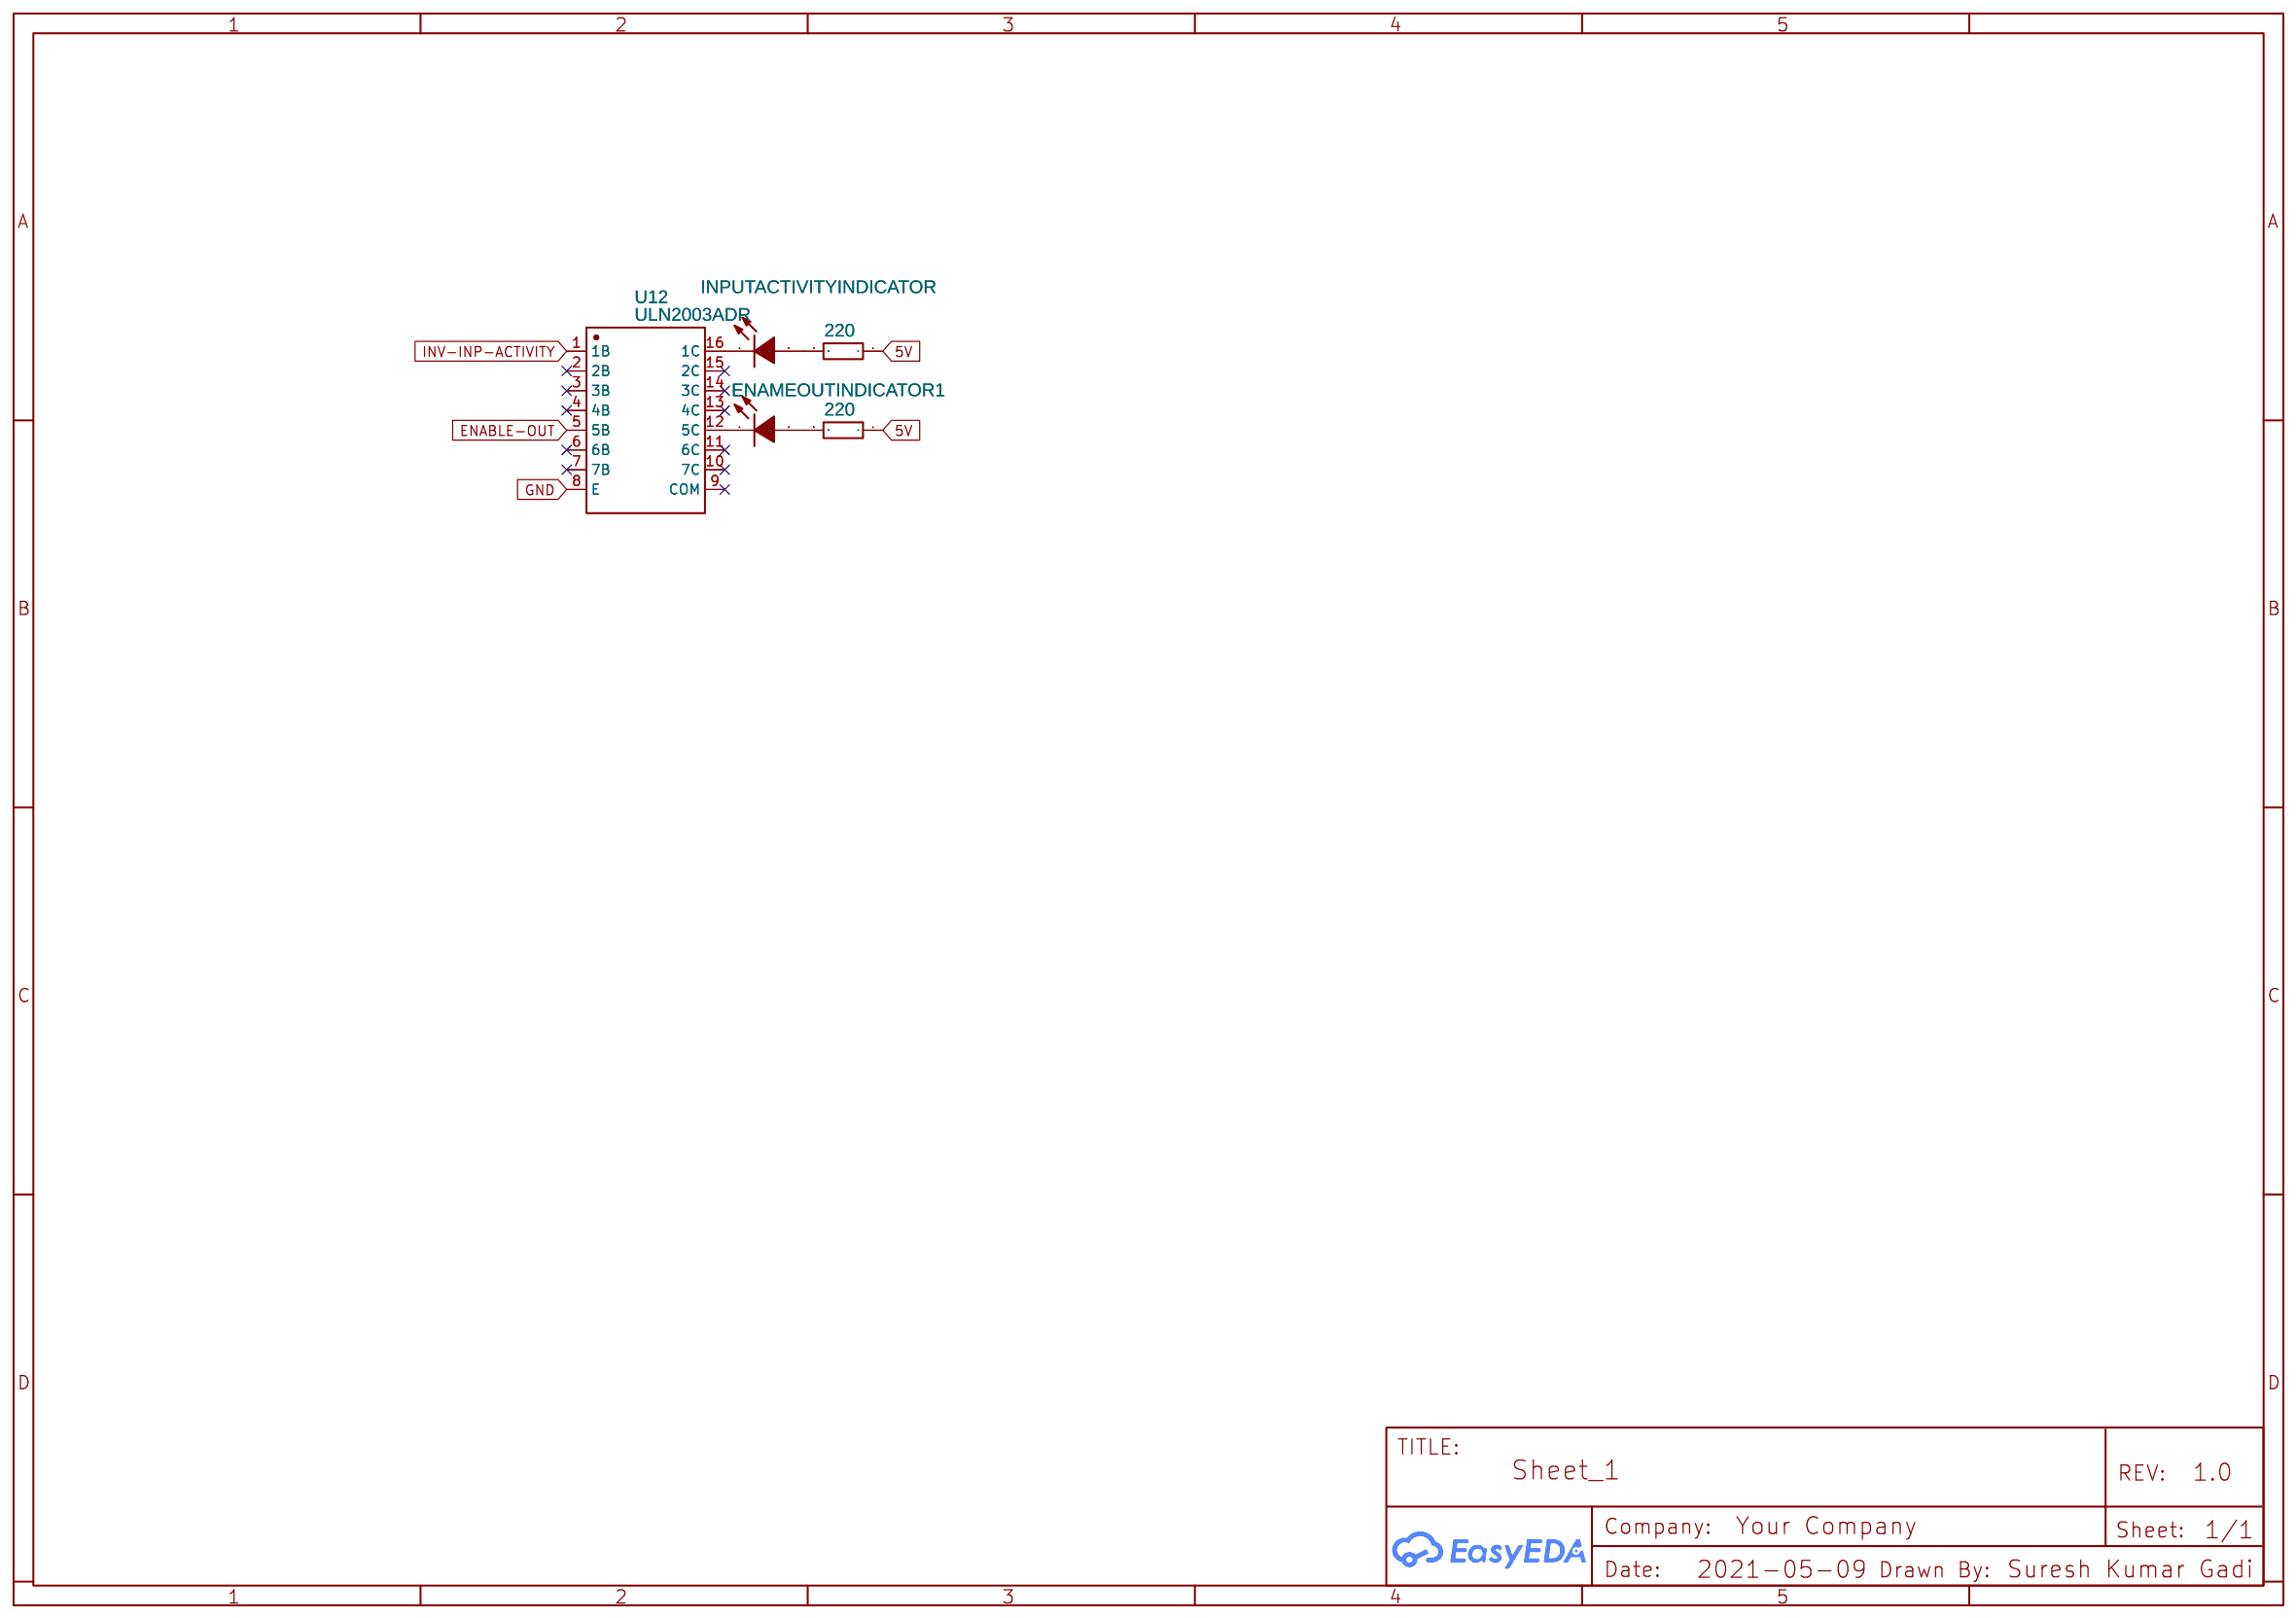
[diagram p8: LEDs]

(export (version "E")
  (design (tool "Eeschema 10.0.6"))
  (components
    (comp (ref "CAP-4-ANALOG-REF")
      (value "100nF")
      (fields
        (field (name "BOM_Manufacturer Part") "CC0603KRX7R9BB104")
        (field (name "BOM_Supplier Part") "C14663")
      )
      (libsource (lib "") (part "CC0603KRX7R9BB104"))
    )
    (comp (ref "CRYSTAL-CAP-1")
      (value "22pF")
      (fields
        (field (name "BOM_Manufacturer Part") "CL21C220JBANNNC")
        (field (name "BOM_Supplier Part") "C1804")
      )
      (libsource (lib "") (part "CL21C220JBANNNC"))
    )
    (comp (ref "CRYSTAL-CAP-2")
      (value "22pF")
      (fields
        (field (name "BOM_Manufacturer Part") "CL21C220JBANNNC")
        (field (name "BOM_Supplier Part") "C1804")
      )
      (libsource (lib "") (part "CL21C220JBANNNC"))
    )
    (comp (ref "H4")
      (value "A2541WR-3P")
      (fields (field (name "BOM_Supplier Part") "C225489"))
      (libsource (lib "") (part "A2541WR-3P"))
    )
    (comp (ref "U3")
      (value "ATMEGA328P-AU")
      (fields (field (name "BOM_Supplier Part") "C14877"))
      (libsource (lib "") (part "ATMEGA328P-AU"))
    )
    (comp (ref "USB2")
      (value "MICRO5.9MMUSB")
      (fields
        (field (name "BOM_Manufacturer Part") "MICRO5.9mmusb")
        (field (name "BOM_Supplier Part") "C393940")
      )
      (libsource (lib "") (part "MICRO5.9MMUSB"))
    )
    (comp (ref "X2")
      (value "16MHz")
      (fields
        (field (name "BOM_Manufacturer Part") "X322516MLB4SI")
        (field (name "BOM_Supplier Part") "C13738")
      )
      (libsource (lib "") (part "X322516MLB4SI"))
    )
    (comp (ref "DECODER-01-08")
      (value "74HC138D,653")
      (fields (field (name "BOM_Supplier Part") "C5602"))
      (libsource (lib "") (part "74HC138D,653_1"))
    )
    (comp (ref "DECODER-09-16")
      (value "74HC138D,653")
      (fields (field (name "BOM_Supplier Part") "C5602"))
      (libsource (lib "") (part "74HC138D,653"))
    )
    (comp (ref "P1")
      (value "2*6P header")
      (fields (field (name "BOM_Supplier Part") "C60565"))
      (libsource (lib "") (part "2*6P header"))
    )
    (comp (ref "P2")
      (value "2*6P header")
      (fields (field (name "BOM_Supplier Part") "C60565"))
      (libsource (lib "") (part "2*6P header"))
    )
    (comp (ref "ENCODER-01-08")
      (value "SN74HC148DR")
      (fields (field (name "BOM_Supplier Part") "C6819"))
      (libsource (lib "") (part "SN74HC148DR"))
    )
    (comp (ref "ENCODER-09-16")
      (value "SN74HC148DR")
      (fields (field (name "BOM_Supplier Part") "C6819"))
      (libsource (lib "") (part "SN74HC148DR_1"))
    )
    (comp (ref "H7")
      (value "A2541WR-2X4P")
      (fields
        (field (name "BOM_Manufacturer Part") "A2541WR-2x4P")
        (field (name "BOM_Supplier Part") "C239335")
      )
      (libsource (lib "") (part "A2541WR-2X4P"))
    )
    (comp (ref "H8")
      (value "A2541WR-2X4P")
      (fields
        (field (name "BOM_Manufacturer Part") "A2541WR-2x4P")
        (field (name "BOM_Supplier Part") "C239335")
      )
      (libsource (lib "") (part "A2541WR-2X4P"))
    )
    (comp (ref "PROG-BUTTON")
      (value "TS-1109S-B-B")
      (fields (field (name "BOM_Supplier Part") "C480315"))
      (libsource (lib "") (part "TS-1109S-B-B"))
    )
    (comp (ref "U5")
      (value "74HC08D,653")
      (fields (field (name "BOM_Supplier Part") "C5593"))
      (libsource (lib "") (part "74HC08D,653"))
    )
    (comp (ref "5V-INDICATOR")
      (value "FC-2012HRK-620D")
      (fields (field (name "BOM_Supplier Part") "C84256"))
      (libsource (lib "") (part "FC-2012HRK-620D_1"))
    )
    (comp (ref "12V-INDICATOR")
      (value "FC-2012HRK-620D")
      (fields (field (name "BOM_Supplier Part") "C84256"))
      (libsource (lib "") (part "FC-2012HRK-620D"))
    )
    (comp (ref "CAP-1-ANALOG-REF")
      (value "100nF")
      (fields
        (field (name "BOM_Manufacturer Part") "CC0603KRX7R9BB104")
        (field (name "BOM_Supplier Part") "C14663")
      )
      (libsource (lib "") (part "CC0603KRX7R9BB104"))
    )
    (comp (ref "CAP-2-ANALOG-REF")
      (value "100nF")
      (fields
        (field (name "BOM_Manufacturer Part") "CC0603KRX7R9BB104")
        (field (name "BOM_Supplier Part") "C14663")
      )
      (libsource (lib "") (part "CC0603KRX7R9BB104_1"))
    )
    (comp (ref "CAP1-FOR-3.3V-PS")
      (value "10uF")
      (fields
        (field (name "BOM_Manufacturer Part") "CL21A106KAYNNNE")
        (field (name "BOM_Supplier Part") "C15850")
      )
      (libsource (lib "") (part "CL21A106KAYNNNE"))
    )
    (comp (ref "CAP2-FOR-3.3V-PS")
      (value "10uF")
      (fields
        (field (name "BOM_Manufacturer Part") "CL21A106KAYNNNE")
        (field (name "BOM_Supplier Part") "C15850")
      )
      (libsource (lib "") (part "CL21A106KAYNNNE_1"))
    )
    (comp (ref "CN1")
      (value "XY118-5.0-2P")
      (fields (field (name "BOM_Supplier Part") "C784922"))
      (libsource (lib "") (part "XY118-5.0-2P"))
    )
    (comp (ref "CN2")
      (value "XY118-5.0-2P")
      (fields (field (name "BOM_Supplier Part") "C784922"))
      (libsource (lib "") (part "XY118-5.0-2P"))
    )
    (comp (ref "R-4-5V-INDICATOR")
      (value "220")
      (fields
        (field (name "BOM_Manufacturer Part") "0805W8F2200T5E")
        (field (name "BOM_Supplier Part") "C17557")
      )
      (libsource (lib "") (part "0805W8F2200T5E"))
    )
    (comp (ref "R-4-12V-INDICATOR")
      (value "750")
      (fields
        (field (name "BOM_Manufacturer Part") "1206W4F7500T5E")
        (field (name "BOM_Supplier Part") "C17985")
      )
      (libsource (lib "") (part "1206W4F7500T5E"))
    )
    (comp (ref "U1")
      (value "AMS1117-3.3")
      (fields (field (name "BOM_Supplier Part") "C6186"))
      (libsource (lib "") (part "AMS1117-3.3"))
    )
    (comp (ref "USB1")
      (value "MICRO5.9MMUSB")
      (fields
        (field (name "BOM_Manufacturer Part") "MICRO5.9mmusb")
        (field (name "BOM_Supplier Part") "C393940")
      )
      (libsource (lib "") (part "MICRO5.9MMUSB"))
    )
    (comp (ref "RN1")
      (value "10K")
      (fields
        (field (name "BOM_Manufacturer Part") "4D03WGJ0103T5E")
        (field (name "BOM_Supplier Part") "C29718")
      )
      (libsource (lib "") (part "4D03WGJ0103T5E"))
    )
    (comp (ref "RN2")
      (value "10K")
      (fields
        (field (name "BOM_Manufacturer Part") "4D03WGJ0103T5E")
        (field (name "BOM_Supplier Part") "C29718")
      )
      (libsource (lib "") (part "4D03WGJ0103T5E"))
    )
    (comp (ref "RN11")
      (value "10K")
      (fields
        (field (name "BOM_Manufacturer Part") "4D03WGJ0103T5E")
        (field (name "BOM_Supplier Part") "C29718")
      )
      (libsource (lib "") (part "4D03WGJ0103T5E"))
    )
    (comp (ref "RN12")
      (value "10K")
      (fields
        (field (name "BOM_Manufacturer Part") "4D03WGJ0103T5E")
        (field (name "BOM_Supplier Part") "C29718")
      )
      (libsource (lib "") (part "4D03WGJ0103T5E"))
    )
    (comp (ref "RN13")
      (value "10K")
      (fields
        (field (name "BOM_Manufacturer Part") "4D03WGJ0103T5E")
        (field (name "BOM_Supplier Part") "C29718")
      )
      (libsource (lib "") (part "4D03WGJ0103T5E"))
    )
    (comp (ref "RN14")
      (value "10K")
      (fields
        (field (name "BOM_Manufacturer Part") "4D03WGJ0103T5E")
        (field (name "BOM_Supplier Part") "C29718")
      )
      (libsource (lib "") (part "4D03WGJ0103T5E"))
    )
    (comp (ref "CARD1")
      (value "TF-15×15")
      (fields (field (name "BOM_Supplier Part") "C111196"))
      (libsource (lib "") (part "TF-15×15"))
    )
    (comp (ref "U6")
      (value "TXB0104PWR")
      (fields (field (name "BOM_Supplier Part") "C60708"))
      (libsource (lib "") (part "TXB0104PWR"))
    )
    (comp (ref "U8")
      (value "74HC04D,653")
      (fields (field (name "BOM_Supplier Part") "C5590"))
      (libsource (lib "") (part "74HC04D,653"))
    )
    (comp (ref "C1")
      (value "100nF")
      (fields
        (field (name "BOM_Manufacturer Part") "CC0603KRX7R9BB104")
        (field (name "BOM_Supplier Part") "C14663")
      )
      (libsource (lib "") (part "CC0603KRX7R9BB104"))
    )
    (comp (ref "C2")
      (value "100nF")
      (fields
        (field (name "BOM_Manufacturer Part") "CC0603KRX7R9BB104")
        (field (name "BOM_Supplier Part") "C14663")
      )
      (libsource (lib "") (part "CC0603KRX7R9BB104"))
    )
    (comp (ref "C5")
      (value "100nF")
      (fields
        (field (name "BOM_Manufacturer Part") "CC0603KRX7R9BB104")
        (field (name "BOM_Supplier Part") "C14663")
      )
      (libsource (lib "") (part "CC0603KRX7R9BB104"))
    )
    (comp (ref "C6")
      (value "100nF")
      (fields
        (field (name "BOM_Manufacturer Part") "CC0603KRX7R9BB104")
        (field (name "BOM_Supplier Part") "C14663")
      )
      (libsource (lib "") (part "CC0603KRX7R9BB104"))
    )
    (comp (ref "C9")
      (value "100nF")
      (fields
        (field (name "BOM_Manufacturer Part") "CC0603KRX7R9BB104")
        (field (name "BOM_Supplier Part") "C14663")
      )
      (libsource (lib "") (part "CC0603KRX7R9BB104"))
    )
    (comp (ref "C10")
      (value "100nF")
      (fields
        (field (name "BOM_Manufacturer Part") "CC0603KRX7R9BB104")
        (field (name "BOM_Supplier Part") "C14663")
      )
      (libsource (lib "") (part "CC0603KRX7R9BB104"))
    )
    (comp (ref "C13")
      (value "100nF")
      (fields
        (field (name "BOM_Manufacturer Part") "CC0603KRX7R9BB104")
        (field (name "BOM_Supplier Part") "C14663")
      )
      (libsource (lib "") (part "CC0603KRX7R9BB104"))
    )
    (comp (ref "C14")
      (value "100nF")
      (fields
        (field (name "BOM_Manufacturer Part") "CC0603KRX7R9BB104")
        (field (name "BOM_Supplier Part") "C14663")
      )
      (libsource (lib "") (part "CC0603KRX7R9BB104"))
    )
    (comp (ref "C17")
      (value "100nF")
      (fields
        (field (name "BOM_Manufacturer Part") "CC0603KRX7R9BB104")
        (field (name "BOM_Supplier Part") "C14663")
      )
      (libsource (lib "") (part "CC0603KRX7R9BB104"))
    )
    (comp (ref "C20")
      (value "100nF")
      (fields
        (field (name "BOM_Manufacturer Part") "CC0603KRX7R9BB104")
        (field (name "BOM_Supplier Part") "C14663")
      )
      (libsource (lib "") (part "CC0603KRX7R9BB104"))
    )
    (comp (ref "H3")
      (value "A2541WR-4P")
      (fields (field (name "BOM_Supplier Part") "C225490"))
      (libsource (lib "") (part "A2541WR-4P"))
    )
    (comp (ref "R5")
      (value "75")
      (fields
        (field (name "BOM_Manufacturer Part") "0402WGF750JTCE")
        (field (name "BOM_Supplier Part") "C25133")
      )
      (libsource (lib "") (part "0402WGF750JTCE"))
    )
    (comp (ref "R6")
      (value "75")
      (fields
        (field (name "BOM_Manufacturer Part") "0402WGF750JTCE")
        (field (name "BOM_Supplier Part") "C25133")
      )
      (libsource (lib "") (part "0402WGF750JTCE"))
    )
    (comp (ref "U11")
      (value "PCA9517ADP,118")
      (fields (field (name "BOM_Supplier Part") "C80799"))
      (libsource (lib "") (part "PCA9517ADP,118"))
    )
    (comp (ref "ENAMEOUTINDICATOR1")
      (value "FC-2012HRK-620D")
      (fields (field (name "BOM_Supplier Part") "C84256"))
      (libsource (lib "") (part "FC-2012HRK-620D_1"))
    )
    (comp (ref "INPUTACTIVITYINDICATOR")
      (value "FC-2012HRK-620D")
      (fields (field (name "BOM_Supplier Part") "C84256"))
      (libsource (lib "") (part "FC-2012HRK-620D"))
    )
    (comp (ref "R-4-1V-INDICATOR")
      (value "220")
      (fields
        (field (name "BOM_Manufacturer Part") "0805W8F2200T5E")
        (field (name "BOM_Supplier Part") "C17557")
      )
      (libsource (lib "") (part "0805W8F2200T5E_1"))
    )
    (comp (ref "RESFORENAMEOUTINDICATOR1")
      (value "220")
      (fields
        (field (name "BOM_Manufacturer Part") "0805W8F2200T5E")
        (field (name "BOM_Supplier Part") "C17557")
      )
      (libsource (lib "") (part "0805W8F2200T5E"))
    )
    (comp (ref "U12")
      (value "ULN2003ADR")
      (fields (field (name "BOM_Supplier Part") "C7512"))
      (libsource (lib "") (part "ULN2003ADR"))
    )
  )
  (nets
    (net (code "1") (name "3.3V") (class "Default")
      (node (ref "C17") (pin "1") (pinfunction "1_1") (pintype "unspecified"))
      (node (ref "CAP1-FOR-3.3V-PS") (pin "1") (pinfunction "1_1") (pintype "input"))
      (node (ref "CARD1") (pin "4") (pinfunction "VDD_4") (pintype "input"))
      (node (ref "U1") (pin "2") (pinfunction "Vout_2") (pintype "unspecified"))
      (node (ref "U1") (pin "4") (pinfunction "Vout_4") (pintype "unspecified"))
      (node (ref "U6") (pin "1") (pinfunction "VCCA_1") (pintype "unspecified"))
      (node (ref "U6") (pin "8") (pinfunction "OE_8") (pintype "unspecified"))
    )
    (net (code "2") (name "5V") (class "Default")
      (node (ref "C1") (pin "1") (pinfunction "1_1") (pintype "unspecified"))
      (node (ref "C10") (pin "1") (pinfunction "1_1") (pintype "unspecified"))
      (node (ref "C13") (pin "1") (pinfunction "1_1") (pintype "unspecified"))
      (node (ref "C14") (pin "1") (pinfunction "1_1") (pintype "unspecified"))
      (node (ref "C2") (pin "1") (pinfunction "1_1") (pintype "unspecified"))
      (node (ref "C20") (pin "1") (pinfunction "1_1") (pintype "unspecified"))
      (node (ref "C5") (pin "1") (pinfunction "1_1") (pintype "unspecified"))
      (node (ref "C6") (pin "1") (pinfunction "1_1") (pintype "unspecified"))
      (node (ref "C9") (pin "1") (pinfunction "1_1") (pintype "unspecified"))
      (node (ref "CAP-1-ANALOG-REF") (pin "1") (pinfunction "1_1") (pintype "unspecified"))
      (node (ref "CAP2-FOR-3.3V-PS") (pin "1") (pinfunction "1_1") (pintype "input"))
      (node (ref "CN2") (pin "1") (pinfunction "1_1") (pintype "unspecified"))
      (node (ref "DECODER-01-08") (pin "16") (pinfunction "VCC_16") (pintype "unspecified"))
      (node (ref "DECODER-09-16") (pin "16") (pinfunction "VCC_16") (pintype "unspecified"))
      (node (ref "ENCODER-01-08") (pin "16") (pinfunction "VCC_16") (pintype "unspecified"))
      (node (ref "ENCODER-09-16") (pin "16") (pinfunction "VCC_16") (pintype "unspecified"))
      (node (ref "H3") (pin "2") (pinfunction "2_2") (pintype "unspecified"))
      (node (ref "P1") (pin "11") (pinfunction "11_11") (pintype "unspecified"))
      (node (ref "P1") (pin "12") (pinfunction "12_12") (pintype "unspecified"))
      (node (ref "P2") (pin "11") (pinfunction "11_11") (pintype "unspecified"))
      (node (ref "P2") (pin "12") (pinfunction "12_12") (pintype "unspecified"))
      (node (ref "R-4-1V-INDICATOR") (pin "1") (pinfunction "1_1") (pintype "input"))
      (node (ref "R-4-5V-INDICATOR") (pin "1") (pinfunction "1_1") (pintype "input"))
      (node (ref "RESFORENAMEOUTINDICATOR1") (pin "1") (pinfunction "1_1") (pintype "input"))
      (node (ref "RN1") (pin "5") (pinfunction "5_5") (pintype "input"))
      (node (ref "RN1") (pin "6") (pinfunction "6_6") (pintype "input"))
      (node (ref "RN1") (pin "7") (pinfunction "7_7") (pintype "input"))
      (node (ref "RN1") (pin "8") (pinfunction "8_8") (pintype "input"))
      (node (ref "RN11") (pin "5") (pinfunction "5_5") (pintype "input"))
      (node (ref "RN11") (pin "6") (pinfunction "6_6") (pintype "input"))
      (node (ref "RN11") (pin "7") (pinfunction "7_7") (pintype "input"))
      (node (ref "RN11") (pin "8") (pinfunction "8_8") (pintype "input"))
      (node (ref "RN12") (pin "5") (pinfunction "5_5") (pintype "input"))
      (node (ref "RN12") (pin "6") (pinfunction "6_6") (pintype "input"))
      (node (ref "RN12") (pin "7") (pinfunction "7_7") (pintype "input"))
      (node (ref "RN12") (pin "8") (pinfunction "8_8") (pintype "input"))
      (node (ref "RN13") (pin "5") (pinfunction "5_5") (pintype "input"))
      (node (ref "RN13") (pin "6") (pinfunction "6_6") (pintype "input"))
      (node (ref "RN13") (pin "7") (pinfunction "7_7") (pintype "input"))
      (node (ref "RN13") (pin "8") (pinfunction "8_8") (pintype "input"))
      (node (ref "RN14") (pin "5") (pinfunction "5_5") (pintype "input"))
      (node (ref "RN14") (pin "6") (pinfunction "6_6") (pintype "input"))
      (node (ref "RN14") (pin "7") (pinfunction "7_7") (pintype "input"))
      (node (ref "RN14") (pin "8") (pinfunction "8_8") (pintype "input"))
      (node (ref "RN2") (pin "5") (pinfunction "5_5") (pintype "input"))
      (node (ref "RN2") (pin "6") (pinfunction "6_6") (pintype "input"))
      (node (ref "RN2") (pin "7") (pinfunction "7_7") (pintype "input"))
      (node (ref "RN2") (pin "8") (pinfunction "8_8") (pintype "input"))
      (node (ref "U1") (pin "3") (pinfunction "Vin_3") (pintype "unspecified"))
      (node (ref "U11") (pin "1") (pinfunction "VCCA_1") (pintype "unspecified"))
      (node (ref "U11") (pin "5") (pinfunction "EN_5") (pintype "unspecified"))
      (node (ref "U11") (pin "8") (pinfunction "VCCB_8") (pintype "unspecified"))
      (node (ref "U3") (pin "18") (pinfunction "AVCC_18") (pintype "unspecified"))
      (node (ref "U3") (pin "30") (pinfunction "PD0(RXD/PCINT16)_30") (pintype "unspecified"))
      (node (ref "U3") (pin "4") (pinfunction "VCC_4") (pintype "unspecified"))
      (node (ref "U3") (pin "6") (pinfunction "VCC_6") (pintype "unspecified"))
      (node (ref "U5") (pin "14") (pinfunction "VCC_14") (pintype "unspecified"))
      (node (ref "U6") (pin "14") (pinfunction "VCCB_14") (pintype "unspecified"))
      (node (ref "U8") (pin "14") (pinfunction "VCC_14") (pintype "unspecified"))
      (node (ref "USB1") (pin "1") (pinfunction "VBUS_1") (pintype "unspecified"))
      (node (ref "USB2") (pin "1") (pinfunction "VBUS_1") (pintype "unspecified"))
    )
    (net (code "3") (name "12V") (class "Default")
      (node (ref "CAP-2-ANALOG-REF") (pin "1") (pinfunction "1_1") (pintype "unspecified"))
      (node (ref "CN1") (pin "2") (pinfunction "2_2") (pintype "unspecified"))
      (node (ref "H4") (pin "3") (pinfunction "3_3") (pintype "unspecified"))
      (node (ref "R-4-12V-INDICATOR") (pin "1") (pinfunction "1_1") (pintype "input"))
    )
    (net (code "4") (name "AND-01-A0") (class "Default")
      (node (ref "ENCODER-01-08") (pin "9") (pinfunction "A0_9") (pintype "unspecified"))
      (node (ref "U5") (pin "1") (pinfunction "1A_1") (pintype "unspecified"))
    )
    (net (code "5") (name "AND-01-A1") (class "Default")
      (node (ref "ENCODER-01-08") (pin "7") (pinfunction "A1_7") (pintype "unspecified"))
      (node (ref "U5") (pin "4") (pinfunction "2A_4") (pintype "unspecified"))
    )
    (net (code "6") (name "AND-01-A2") (class "Default")
      (node (ref "ENCODER-01-08") (pin "6") (pinfunction "A2_6") (pintype "unspecified"))
      (node (ref "U5") (pin "9") (pinfunction "3A_9") (pintype "unspecified"))
    )
    (net (code "7") (name "AND-02-A0") (class "Default")
      (node (ref "ENCODER-09-16") (pin "9") (pinfunction "A0_9") (pintype "unspecified"))
      (node (ref "U5") (pin "2") (pinfunction "1B_2") (pintype "unspecified"))
    )
    (net (code "8") (name "AND-02-A1") (class "Default")
      (node (ref "ENCODER-09-16") (pin "7") (pinfunction "A1_7") (pintype "unspecified"))
      (node (ref "U5") (pin "5") (pinfunction "2B_5") (pintype "unspecified"))
    )
    (net (code "9") (name "AND-02-A2") (class "Default")
      (node (ref "ENCODER-09-16") (pin "6") (pinfunction "A2_6") (pintype "unspecified"))
      (node (ref "U5") (pin "10") (pinfunction "3B_10") (pintype "unspecified"))
    )
    (net (code "10") (name "AREF") (class "Default")
      (node (ref "CAP-4-ANALOG-REF") (pin "1") (pinfunction "1_1") (pintype "unspecified"))
      (node (ref "U3") (pin "20") (pinfunction "AREF_20") (pintype "unspecified"))
    )
    (net (code "11") (name "BTN-01") (class "Default")
      (node (ref "ENCODER-01-08") (pin "10") (pinfunction "0_10") (pintype "unspecified"))
      (node (ref "H7") (pin "1") (pinfunction "1_1") (pintype "unspecified"))
      (node (ref "RN11") (pin "4") (pinfunction "4_4") (pintype "input"))
    )
    (net (code "12") (name "BTN-02") (class "Default")
      (node (ref "ENCODER-01-08") (pin "11") (pinfunction "1_11") (pintype "unspecified"))
      (node (ref "H7") (pin "2") (pinfunction "2_2") (pintype "unspecified"))
      (node (ref "RN11") (pin "3") (pinfunction "3_3") (pintype "input"))
    )
    (net (code "13") (name "BTN-03") (class "Default")
      (node (ref "ENCODER-01-08") (pin "12") (pinfunction "2_12") (pintype "unspecified"))
      (node (ref "H7") (pin "3") (pinfunction "3_3") (pintype "unspecified"))
      (node (ref "RN11") (pin "2") (pinfunction "2_2") (pintype "input"))
    )
    (net (code "14") (name "BTN-04") (class "Default")
      (node (ref "ENCODER-01-08") (pin "13") (pinfunction "3_13") (pintype "unspecified"))
      (node (ref "H7") (pin "4") (pinfunction "4_4") (pintype "unspecified"))
      (node (ref "RN11") (pin "1") (pinfunction "1_1") (pintype "input"))
    )
    (net (code "15") (name "BTN-05") (class "Default")
      (node (ref "ENCODER-01-08") (pin "1") (pinfunction "4_1") (pintype "unspecified"))
      (node (ref "H7") (pin "5") (pinfunction "5_5") (pintype "unspecified"))
      (node (ref "RN12") (pin "4") (pinfunction "4_4") (pintype "input"))
    )
    (net (code "16") (name "BTN-06") (class "Default")
      (node (ref "ENCODER-01-08") (pin "2") (pinfunction "5_2") (pintype "unspecified"))
      (node (ref "H7") (pin "6") (pinfunction "6_6") (pintype "unspecified"))
      (node (ref "RN12") (pin "3") (pinfunction "3_3") (pintype "input"))
    )
    (net (code "17") (name "BTN-07") (class "Default")
      (node (ref "ENCODER-01-08") (pin "3") (pinfunction "6_3") (pintype "unspecified"))
      (node (ref "H7") (pin "7") (pinfunction "7_7") (pintype "unspecified"))
      (node (ref "RN12") (pin "2") (pinfunction "2_2") (pintype "input"))
    )
    (net (code "18") (name "BTN-08") (class "Default")
      (node (ref "ENCODER-01-08") (pin "4") (pinfunction "7_4") (pintype "unspecified"))
      (node (ref "H7") (pin "8") (pinfunction "8_8") (pintype "unspecified"))
      (node (ref "RN12") (pin "1") (pinfunction "1_1") (pintype "input"))
    )
    (net (code "19") (name "BTN-09") (class "Default")
      (node (ref "ENCODER-09-16") (pin "10") (pinfunction "0_10") (pintype "unspecified"))
      (node (ref "H8") (pin "1") (pinfunction "1_1") (pintype "unspecified"))
      (node (ref "RN13") (pin "4") (pinfunction "4_4") (pintype "input"))
    )
    (net (code "20") (name "BTN-10") (class "Default")
      (node (ref "ENCODER-09-16") (pin "11") (pinfunction "1_11") (pintype "unspecified"))
      (node (ref "H8") (pin "2") (pinfunction "2_2") (pintype "unspecified"))
      (node (ref "RN13") (pin "3") (pinfunction "3_3") (pintype "input"))
    )
    (net (code "21") (name "BTN-11") (class "Default")
      (node (ref "ENCODER-09-16") (pin "12") (pinfunction "2_12") (pintype "unspecified"))
      (node (ref "H8") (pin "3") (pinfunction "3_3") (pintype "unspecified"))
      (node (ref "RN13") (pin "2") (pinfunction "2_2") (pintype "input"))
    )
    (net (code "22") (name "BTN-12") (class "Default")
      (node (ref "ENCODER-09-16") (pin "13") (pinfunction "3_13") (pintype "unspecified"))
      (node (ref "H8") (pin "4") (pinfunction "4_4") (pintype "unspecified"))
      (node (ref "RN13") (pin "1") (pinfunction "1_1") (pintype "input"))
    )
    (net (code "23") (name "BTN-13") (class "Default")
      (node (ref "ENCODER-09-16") (pin "1") (pinfunction "4_1") (pintype "unspecified"))
      (node (ref "H8") (pin "5") (pinfunction "5_5") (pintype "unspecified"))
      (node (ref "RN14") (pin "4") (pinfunction "4_4") (pintype "input"))
    )
    (net (code "24") (name "BTN-14") (class "Default")
      (node (ref "ENCODER-09-16") (pin "2") (pinfunction "5_2") (pintype "unspecified"))
      (node (ref "H8") (pin "6") (pinfunction "6_6") (pintype "unspecified"))
      (node (ref "RN14") (pin "3") (pinfunction "3_3") (pintype "input"))
    )
    (net (code "25") (name "BTN-15") (class "Default")
      (node (ref "ENCODER-09-16") (pin "3") (pinfunction "6_3") (pintype "unspecified"))
      (node (ref "H8") (pin "7") (pinfunction "7_7") (pintype "unspecified"))
      (node (ref "RN14") (pin "2") (pinfunction "2_2") (pintype "input"))
    )
    (net (code "26") (name "BTN-16") (class "Default")
      (node (ref "ENCODER-09-16") (pin "4") (pinfunction "7_4") (pintype "unspecified"))
      (node (ref "H8") (pin "8") (pinfunction "8_8") (pintype "unspecified"))
      (node (ref "RN14") (pin "1") (pinfunction "1_1") (pintype "input"))
    )
    (net (code "27") (name "COIN") (class "Default")
      (node (ref "H4") (pin "2") (pinfunction "2_2") (pintype "unspecified"))
      (node (ref "RN2") (pin "1") (pinfunction "1_1") (pintype "input"))
      (node (ref "U3") (pin "32") (pinfunction "PD2(INT0/PCINT18)_32") (pintype "unspecified"))
    )
    (net (code "28") (name "CONFIG") (class "Default")
      (node (ref "PROG-BUTTON") (pin "1") (pinfunction "1_1") (pintype "unspecified"))
      (node (ref "PROG-BUTTON") (pin "2") (pinfunction "2_2") (pintype "unspecified"))
      (node (ref "RN2") (pin "2") (pinfunction "2_2") (pintype "input"))
      (node (ref "U3") (pin "1") (pinfunction "(PCINT19/OC2B/INT1)PD3_1") (pintype "unspecified"))
    )
    (net (code "29") (name "DISP-SCL") (class "Default")
      (node (ref "H3") (pin "4") (pinfunction "4_4") (pintype "unspecified"))
      (node (ref "R5") (pin "1") (pinfunction "1_1") (pintype "input"))
      (node (ref "RN1") (pin "4") (pinfunction "4_4") (pintype "input"))
    )
    (net (code "30") (name "DISP-SDA") (class "Default")
      (node (ref "H3") (pin "3") (pinfunction "3_3") (pintype "unspecified"))
      (node (ref "R6") (pin "1") (pinfunction "1_1") (pintype "input"))
      (node (ref "RN1") (pin "3") (pinfunction "3_3") (pintype "input"))
    )
    (net (code "31") (name "ENABLE-OUT") (class "Default")
      (node (ref "DECODER-01-08") (pin "6") (pinfunction "E3_6") (pintype "unspecified"))
      (node (ref "DECODER-09-16") (pin "6") (pinfunction "E3_6") (pintype "unspecified"))
      (node (ref "U12") (pin "5") (pinfunction "5B_5") (pintype "unspecified"))
      (node (ref "U3") (pin "9") (pinfunction "(PCINT21/OC0B/T1)PD5_9") (pintype "unspecified"))
    )
    (net (code "32") (name "ENC-GS-01") (class "Default")
      (node (ref "ENCODER-01-08") (pin "14") (pinfunction "GS_14") (pintype "unspecified"))
      (node (ref "U5") (pin "13") (pinfunction "4B_13") (pintype "unspecified"))
    )
    (net (code "33") (name "GND") (class "Default")
      (node (ref "12V-INDICATOR") (pin "1") (pinfunction "-_1") (pintype "unspecified"))
      (node (ref "5V-INDICATOR") (pin "1") (pinfunction "-_1") (pintype "unspecified"))
      (node (ref "C1") (pin "2") (pinfunction "2_2") (pintype "unspecified"))
      (node (ref "C10") (pin "2") (pinfunction "2_2") (pintype "unspecified"))
      (node (ref "C13") (pin "2") (pinfunction "2_2") (pintype "unspecified"))
      (node (ref "C14") (pin "2") (pinfunction "2_2") (pintype "unspecified"))
      (node (ref "C17") (pin "2") (pinfunction "2_2") (pintype "unspecified"))
      (node (ref "C2") (pin "2") (pinfunction "2_2") (pintype "unspecified"))
      (node (ref "C20") (pin "2") (pinfunction "2_2") (pintype "unspecified"))
      (node (ref "C5") (pin "2") (pinfunction "2_2") (pintype "unspecified"))
      (node (ref "C6") (pin "2") (pinfunction "2_2") (pintype "unspecified"))
      (node (ref "C9") (pin "2") (pinfunction "2_2") (pintype "unspecified"))
      (node (ref "CAP-1-ANALOG-REF") (pin "2") (pinfunction "2_2") (pintype "unspecified"))
      (node (ref "CAP-2-ANALOG-REF") (pin "2") (pinfunction "2_2") (pintype "unspecified"))
      (node (ref "CAP-4-ANALOG-REF") (pin "2") (pinfunction "2_2") (pintype "unspecified"))
      (node (ref "CAP1-FOR-3.3V-PS") (pin "2") (pinfunction "2_2") (pintype "input"))
      (node (ref "CAP2-FOR-3.3V-PS") (pin "2") (pinfunction "2_2") (pintype "input"))
      (node (ref "CARD1") (pin "10") (pinfunction "G3_10") (pintype "input"))
      (node (ref "CARD1") (pin "11") (pinfunction "G4_11") (pintype "input"))
      (node (ref "CARD1") (pin "12") (pinfunction "G1_12") (pintype "input"))
      (node (ref "CARD1") (pin "13") (pinfunction "G2_13") (pintype "input"))
      (node (ref "CARD1") (pin "6") (pinfunction "VSS_6") (pintype "input"))
      (node (ref "CN1") (pin "1") (pinfunction "1_1") (pintype "unspecified"))
      (node (ref "CN2") (pin "2") (pinfunction "2_2") (pintype "unspecified"))
      (node (ref "CRYSTAL-CAP-1") (pin "1") (pinfunction "1_1") (pintype "input"))
      (node (ref "CRYSTAL-CAP-2") (pin "1") (pinfunction "1_1") (pintype "input"))
      (node (ref "DECODER-01-08") (pin "5") (pinfunction "E2#_5") (pintype "unspecified"))
      (node (ref "DECODER-01-08") (pin "8") (pinfunction "GND_8") (pintype "unspecified"))
      (node (ref "DECODER-09-16") (pin "5") (pinfunction "E2#_5") (pintype "unspecified"))
      (node (ref "DECODER-09-16") (pin "8") (pinfunction "GND_8") (pintype "unspecified"))
      (node (ref "ENCODER-01-08") (pin "8") (pinfunction "GND_8") (pintype "unspecified"))
      (node (ref "ENCODER-09-16") (pin "5") (pinfunction "EI_5") (pintype "unspecified"))
      (node (ref "ENCODER-09-16") (pin "8") (pinfunction "GND_8") (pintype "unspecified"))
      (node (ref "H3") (pin "1") (pinfunction "1_1") (pintype "unspecified"))
      (node (ref "H4") (pin "1") (pinfunction "1_1") (pintype "unspecified"))
      (node (ref "P1") (pin "1") (pinfunction "1_1") (pintype "unspecified"))
      (node (ref "P1") (pin "2") (pinfunction "2_2") (pintype "unspecified"))
      (node (ref "P2") (pin "1") (pinfunction "1_1") (pintype "unspecified"))
      (node (ref "P2") (pin "2") (pinfunction "2_2") (pintype "unspecified"))
      (node (ref "PROG-BUTTON") (pin "3") (pinfunction "3_3") (pintype "unspecified"))
      (node (ref "PROG-BUTTON") (pin "4") (pinfunction "4_4") (pintype "unspecified"))
      (node (ref "U1") (pin "1") (pinfunction "GND/ADJ_1") (pintype "unspecified"))
      (node (ref "U11") (pin "4") (pinfunction "GND_4") (pintype "unspecified"))
      (node (ref "U12") (pin "8") (pinfunction "E_8") (pintype "unspecified"))
      (node (ref "U3") (pin "21") (pinfunction "GND_21") (pintype "unspecified"))
      (node (ref "U3") (pin "3") (pinfunction "GND_3") (pintype "unspecified"))
      (node (ref "U3") (pin "5") (pinfunction "GND_5") (pintype "unspecified"))
      (node (ref "U5") (pin "7") (pinfunction "GND_7") (pintype "unspecified"))
      (node (ref "U6") (pin "7") (pinfunction "GND_7") (pintype "unspecified"))
      (node (ref "U8") (pin "7") (pinfunction "GND_7") (pintype "unspecified"))
      (node (ref "USB1") (pin "5") (pinfunction "GND_5") (pintype "unspecified"))
      (node (ref "USB1") (pin "6") (pinfunction "6_6") (pintype "unspecified"))
      (node (ref "USB2") (pin "6") (pinfunction "6_6") (pintype "unspecified"))
      (node (ref "X2") (pin "2") (pinfunction "GND_2") (pintype "unspecified"))
      (node (ref "X2") (pin "4") (pinfunction "GND_4") (pintype "unspecified"))
    )
    (net (code "34") (name "ICSP-MISO") (class "Default")
      (node (ref "U3") (pin "16") (pinfunction "(PCINT4/MISO)PB4_16") (pintype "unspecified"))
      (node (ref "U6") (pin "13") (pinfunction "B1_13") (pintype "unspecified"))
      (node (ref "USB2") (pin "2") (pinfunction "D-_2") (pintype "unspecified"))
    )
    (net (code "35") (name "ICSP-MOSI") (class "Default")
      (node (ref "RN2") (pin "3") (pinfunction "3_3") (pintype "input"))
      (node (ref "U3") (pin "15") (pinfunction "(PCINT3/OC2A/MOSI)PB3_15") (pintype "unspecified"))
      (node (ref "U6") (pin "11") (pinfunction "B3_11") (pintype "unspecified"))
      (node (ref "USB2") (pin "4") (pinfunction "ID_4") (pintype "unspecified"))
    )
    (net (code "36") (name "ICSP-RESET") (class "Default")
      (node (ref "RN2") (pin "4") (pinfunction "4_4") (pintype "input"))
      (node (ref "U3") (pin "29") (pinfunction "PC6(RESET#/PCINT14)_29") (pintype "unspecified"))
      (node (ref "U8") (pin "1") (pinfunction "1A_1") (pintype "unspecified"))
      (node (ref "USB2") (pin "5") (pinfunction "GND_5") (pintype "unspecified"))
    )
    (net (code "37") (name "ICSP-SCK") (class "Default")
      (node (ref "U3") (pin "17") (pinfunction "PB5(SCK/PCINT5)_17") (pintype "unspecified"))
      (node (ref "U6") (pin "12") (pinfunction "B2_12") (pintype "unspecified"))
      (node (ref "USB2") (pin "3") (pinfunction "D+_3") (pintype "unspecified"))
    )
    (net (code "38") (name "INP-00") (class "Default")
      (node (ref "U3") (pin "25") (pinfunction "PC2(ADC2/PCINT10)_25") (pintype "unspecified"))
      (node (ref "U5") (pin "3") (pinfunction "1Y_3") (pintype "unspecified"))
    )
    (net (code "39") (name "INP-01") (class "Default")
      (node (ref "U3") (pin "26") (pinfunction "PC3(ADC3/PCINT11)_26") (pintype "unspecified"))
      (node (ref "U5") (pin "6") (pinfunction "2Y_6") (pintype "unspecified"))
    )
    (net (code "40") (name "INP-02") (class "Default")
      (node (ref "U3") (pin "2") (pinfunction "(PCINT20/XCK/T0)PD4_2") (pintype "unspecified"))
      (node (ref "U3") (pin "23") (pinfunction "PC0(ADC0/PCINT8)_23") (pintype "unspecified"))
      (node (ref "U5") (pin "8") (pinfunction "3Y_8") (pintype "unspecified"))
    )
    (net (code "41") (name "INP-03") (class "Default")
      (node (ref "ENCODER-01-08") (pin "5") (pinfunction "EI_5") (pintype "unspecified"))
      (node (ref "ENCODER-09-16") (pin "14") (pinfunction "GS_14") (pintype "unspecified"))
      (node (ref "ENCODER-09-16") (pin "15") (pinfunction "EO_15") (pintype "unspecified"))
      (node (ref "U3") (pin "24") (pinfunction "PC1(ADC1/PCINT9)_24") (pintype "unspecified"))
      (node (ref "U5") (pin "12") (pinfunction "4A_12") (pintype "unspecified"))
    )
    (net (code "42") (name "INP-ACTIVITY") (class "Default")
      (node (ref "U3") (pin "31") (pinfunction "PD1(TXD/PCINT17)_31") (pintype "unspecified"))
      (node (ref "U5") (pin "11") (pinfunction "4Y_11") (pintype "unspecified"))
      (node (ref "U8") (pin "11") (pinfunction "5A_11") (pintype "unspecified"))
    )
    (net (code "43") (name "INV-INP-ACTIVITY") (class "Default")
      (node (ref "U12") (pin "1") (pinfunction "1B_1") (pintype "unspecified"))
      (node (ref "U8") (pin "10") (pinfunction "5Y_10") (pintype "unspecified"))
    )
    (net (code "44") (name "Net-(5V-INDICATOR-+)") (class "Default")
      (node (ref "5V-INDICATOR") (pin "2") (pinfunction "+_2") (pintype "unspecified"))
      (node (ref "R-4-5V-INDICATOR") (pin "2") (pinfunction "2_2") (pintype "input"))
    )
    (net (code "45") (name "Net-(12V-INDICATOR-+)") (class "Default")
      (node (ref "12V-INDICATOR") (pin "2") (pinfunction "+_2") (pintype "unspecified"))
      (node (ref "R-4-12V-INDICATOR") (pin "2") (pinfunction "2_2") (pintype "input"))
    )
    (net (code "46") (name "Net-(ENAMEOUTINDICATOR1-+)") (class "Default")
      (node (ref "ENAMEOUTINDICATOR1") (pin "2") (pinfunction "+_2") (pintype "unspecified"))
      (node (ref "RESFORENAMEOUTINDICATOR1") (pin "2") (pinfunction "2_2") (pintype "input"))
    )
    (net (code "47") (name "Net-(ENAMEOUTINDICATOR1--)") (class "Default")
      (node (ref "ENAMEOUTINDICATOR1") (pin "1") (pinfunction "-_1") (pintype "unspecified"))
      (node (ref "U12") (pin "12") (pinfunction "5C_12") (pintype "unspecified"))
    )
    (net (code "48") (name "Net-(INPUTACTIVITYINDICATOR-+)") (class "Default")
      (node (ref "INPUTACTIVITYINDICATOR") (pin "2") (pinfunction "+_2") (pintype "unspecified"))
      (node (ref "R-4-1V-INDICATOR") (pin "2") (pinfunction "2_2") (pintype "input"))
    )
    (net (code "49") (name "Net-(INPUTACTIVITYINDICATOR--)") (class "Default")
      (node (ref "INPUTACTIVITYINDICATOR") (pin "1") (pinfunction "-_1") (pintype "unspecified"))
      (node (ref "U12") (pin "16") (pinfunction "1C_16") (pintype "unspecified"))
    )
    (net (code "50") (name "Net-(U11-SCLA)") (class "Default")
      (node (ref "R5") (pin "2") (pinfunction "2_2") (pintype "input"))
      (node (ref "U11") (pin "2") (pinfunction "SCLA_2") (pintype "unspecified"))
    )
    (net (code "51") (name "Net-(U11-SDAA)") (class "Default")
      (node (ref "R6") (pin "2") (pinfunction "2_2") (pintype "input"))
      (node (ref "U11") (pin "3") (pinfunction "SDAA_3") (pintype "unspecified"))
    )
    (net (code "52") (name "OPP-RESET") (class "Default")
      (node (ref "U6") (pin "10") (pinfunction "B4_10") (pintype "unspecified"))
      (node (ref "U8") (pin "2") (pinfunction "1Y_2") (pintype "unspecified"))
    )
    (net (code "53") (name "OUT-00") (class "Default")
      (node (ref "DECODER-01-08") (pin "1") (pinfunction "A0_1") (pintype "unspecified"))
      (node (ref "DECODER-09-16") (pin "1") (pinfunction "A0_1") (pintype "unspecified"))
      (node (ref "U3") (pin "14") (pinfunction "(PCINT2/SS#/OC1B)PB2_14") (pintype "unspecified"))
    )
    (net (code "54") (name "OUT-01") (class "Default")
      (node (ref "DECODER-01-08") (pin "2") (pinfunction "A1_2") (pintype "unspecified"))
      (node (ref "DECODER-09-16") (pin "2") (pinfunction "A1_2") (pintype "unspecified"))
      (node (ref "U3") (pin "13") (pinfunction "(PCINT1/OC1A)PB1_13") (pintype "unspecified"))
    )
    (net (code "55") (name "OUT-02") (class "Default")
      (node (ref "DECODER-01-08") (pin "3") (pinfunction "A2_3") (pintype "unspecified"))
      (node (ref "DECODER-09-16") (pin "3") (pinfunction "A2_3") (pintype "unspecified"))
      (node (ref "U3") (pin "12") (pinfunction "(PCINT0/CLKO/ICP1)PB0_12") (pintype "unspecified"))
    )
    (net (code "56") (name "OUT-03") (class "Default")
      (node (ref "DECODER-01-08") (pin "4") (pinfunction "E1#_4") (pintype "unspecified"))
      (node (ref "DECODER-09-16") (pin "4") (pinfunction "E1#_4") (pintype "unspecified"))
      (node (ref "U3") (pin "11") (pinfunction "(PCINT23/AIN1)PD7_11") (pintype "unspecified"))
    )
    (net (code "57") (name "RELAY-01") (class "Default")
      (node (ref "DECODER-01-08") (pin "15") (pinfunction "Y0#_15") (pintype "unspecified"))
      (node (ref "P1") (pin "3") (pinfunction "3_3") (pintype "unspecified"))
    )
    (net (code "58") (name "RELAY-02") (class "Default")
      (node (ref "DECODER-01-08") (pin "14") (pinfunction "Y1#_14") (pintype "unspecified"))
      (node (ref "P1") (pin "4") (pinfunction "4_4") (pintype "unspecified"))
    )
    (net (code "59") (name "RELAY-03") (class "Default")
      (node (ref "DECODER-01-08") (pin "13") (pinfunction "Y2#_13") (pintype "unspecified"))
      (node (ref "P1") (pin "5") (pinfunction "5_5") (pintype "unspecified"))
    )
    (net (code "60") (name "RELAY-04") (class "Default")
      (node (ref "DECODER-01-08") (pin "12") (pinfunction "Y3#_12") (pintype "unspecified"))
      (node (ref "P1") (pin "6") (pinfunction "6_6") (pintype "unspecified"))
    )
    (net (code "61") (name "RELAY-05") (class "Default")
      (node (ref "DECODER-01-08") (pin "11") (pinfunction "Y4#_11") (pintype "unspecified"))
      (node (ref "P1") (pin "7") (pinfunction "7_7") (pintype "unspecified"))
    )
    (net (code "62") (name "RELAY-06") (class "Default")
      (node (ref "DECODER-01-08") (pin "10") (pinfunction "Y5#_10") (pintype "unspecified"))
      (node (ref "P1") (pin "8") (pinfunction "8_8") (pintype "unspecified"))
    )
    (net (code "63") (name "RELAY-07") (class "Default")
      (node (ref "DECODER-01-08") (pin "9") (pinfunction "Y6#_9") (pintype "unspecified"))
      (node (ref "P1") (pin "9") (pinfunction "9_9") (pintype "unspecified"))
    )
    (net (code "64") (name "RELAY-08") (class "Default")
      (node (ref "DECODER-01-08") (pin "7") (pinfunction "Y7#_7") (pintype "unspecified"))
      (node (ref "P1") (pin "10") (pinfunction "10_10") (pintype "unspecified"))
    )
    (net (code "65") (name "RELAY-09") (class "Default")
      (node (ref "DECODER-09-16") (pin "15") (pinfunction "Y0#_15") (pintype "unspecified"))
      (node (ref "P2") (pin "3") (pinfunction "3_3") (pintype "unspecified"))
    )
    (net (code "66") (name "RELAY-10") (class "Default")
      (node (ref "DECODER-09-16") (pin "14") (pinfunction "Y1#_14") (pintype "unspecified"))
      (node (ref "P2") (pin "4") (pinfunction "4_4") (pintype "unspecified"))
    )
    (net (code "67") (name "RELAY-11") (class "Default")
      (node (ref "DECODER-09-16") (pin "13") (pinfunction "Y2#_13") (pintype "unspecified"))
      (node (ref "P2") (pin "5") (pinfunction "5_5") (pintype "unspecified"))
    )
    (net (code "68") (name "RELAY-12") (class "Default")
      (node (ref "DECODER-09-16") (pin "12") (pinfunction "Y3#_12") (pintype "unspecified"))
      (node (ref "P2") (pin "6") (pinfunction "6_6") (pintype "unspecified"))
    )
    (net (code "69") (name "RELAY-13") (class "Default")
      (node (ref "DECODER-09-16") (pin "11") (pinfunction "Y4#_11") (pintype "unspecified"))
      (node (ref "P2") (pin "7") (pinfunction "7_7") (pintype "unspecified"))
    )
    (net (code "70") (name "RELAY-14") (class "Default")
      (node (ref "DECODER-09-16") (pin "10") (pinfunction "Y5#_10") (pintype "unspecified"))
      (node (ref "P2") (pin "8") (pinfunction "8_8") (pintype "unspecified"))
    )
    (net (code "71") (name "RELAY-15") (class "Default")
      (node (ref "DECODER-09-16") (pin "9") (pinfunction "Y6#_9") (pintype "unspecified"))
      (node (ref "P2") (pin "9") (pinfunction "9_9") (pintype "unspecified"))
    )
    (net (code "72") (name "RELAY-16") (class "Default")
      (node (ref "DECODER-09-16") (pin "7") (pinfunction "Y7#_7") (pintype "unspecified"))
      (node (ref "P2") (pin "10") (pinfunction "10_10") (pintype "unspecified"))
    )
    (net (code "73") (name "SCL") (class "Default")
      (node (ref "RN1") (pin "1") (pinfunction "1_1") (pintype "input"))
      (node (ref "U11") (pin "7") (pinfunction "SCLB_7") (pintype "unspecified"))
      (node (ref "U3") (pin "28") (pinfunction "PC5(ADC5/SCL/PCINT13)_28") (pintype "unspecified"))
    )
    (net (code "74") (name "SD-PIN-2") (class "Default")
      (node (ref "CARD1") (pin "2") (pinfunction "CD/DAT3_2") (pintype "input"))
      (node (ref "U6") (pin "5") (pinfunction "A4_5") (pintype "unspecified"))
    )
    (net (code "75") (name "SD-PIN-3") (class "Default")
      (node (ref "CARD1") (pin "3") (pinfunction "CMD_3") (pintype "input"))
      (node (ref "U6") (pin "4") (pinfunction "A3_4") (pintype "unspecified"))
    )
    (net (code "76") (name "SD-PIN-5") (class "Default")
      (node (ref "CARD1") (pin "5") (pinfunction "CLK_5") (pintype "input"))
      (node (ref "U6") (pin "3") (pinfunction "A2_3") (pintype "unspecified"))
    )
    (net (code "77") (name "SD-PIN-7") (class "Default")
      (node (ref "CARD1") (pin "7") (pinfunction "DAT0_7") (pintype "input"))
      (node (ref "U6") (pin "2") (pinfunction "A1_2") (pintype "unspecified"))
    )
    (net (code "78") (name "SDA") (class "Default")
      (node (ref "RN1") (pin "2") (pinfunction "2_2") (pintype "input"))
      (node (ref "U11") (pin "6") (pinfunction "SDAB_6") (pintype "unspecified"))
      (node (ref "U3") (pin "27") (pinfunction "PC4(ADC4/SDA/PCINT12)_27") (pintype "unspecified"))
    )
    (net (code "79") (name "XTAL1") (class "Default")
      (node (ref "CRYSTAL-CAP-1") (pin "2") (pinfunction "2_2") (pintype "input"))
      (node (ref "U3") (pin "7") (pinfunction "(PCINT6/XTAL1/TOSC1)PB6_7") (pintype "unspecified"))
      (node (ref "X2") (pin "3") (pinfunction "OSC2_3") (pintype "unspecified"))
    )
    (net (code "80") (name "XTAL2") (class "Default")
      (node (ref "CRYSTAL-CAP-2") (pin "2") (pinfunction "2_2") (pintype "input"))
      (node (ref "U3") (pin "8") (pinfunction "(PCINT7/XTAL2/TOSC2)PB7_8") (pintype "unspecified"))
      (node (ref "X2") (pin "1") (pinfunction "OSC1_1") (pintype "unspecified"))
    )
    (net (code "81") (name "unconnected-(CARD1-CD-Pad9)") (class "Default")
      (node (ref "CARD1") (pin "9") (pinfunction "CD_9") (pintype "input+no_connect"))
    )
    (net (code "82") (name "unconnected-(CARD1-DAT1-Pad8)") (class "Default")
      (node (ref "CARD1") (pin "8") (pinfunction "DAT1_8") (pintype "input+no_connect"))
    )
    (net (code "83") (name "unconnected-(CARD1-DAT2-Pad1)") (class "Default")
      (node (ref "CARD1") (pin "1") (pinfunction "DAT2_1") (pintype "input+no_connect"))
    )
    (net (code "84") (name "unconnected-(ENCODER-01-08-EO-Pad15)") (class "Default")
      (node (ref "ENCODER-01-08") (pin "15") (pinfunction "EO_15") (pintype "unspecified+no_connect"))
    )
    (net (code "85") (name "unconnected-(U3-(PCINT22{slash}OC0A{slash}AIN0)PD6-Pad10)") (class "Default")
      (node (ref "U3") (pin "10") (pinfunction "(PCINT22/OC0A/AIN0)PD6_10") (pintype "unspecified+no_connect"))
    )
    (net (code "86") (name "unconnected-(U3-ADC6-Pad19)") (class "Default")
      (node (ref "U3") (pin "19") (pinfunction "ADC6_19") (pintype "unspecified+no_connect"))
    )
    (net (code "87") (name "unconnected-(U3-ADC7-Pad22)") (class "Default")
      (node (ref "U3") (pin "22") (pinfunction "ADC7_22") (pintype "unspecified+no_connect"))
    )
    (net (code "88") (name "unconnected-(U6-NC-Pad6)") (class "Default")
      (node (ref "U6") (pin "6") (pinfunction "NC_6") (pintype "unspecified+no_connect"))
    )
    (net (code "89") (name "unconnected-(U6-NC-Pad9)") (class "Default")
      (node (ref "U6") (pin "9") (pinfunction "NC_9") (pintype "unspecified+no_connect"))
    )
    (net (code "90") (name "unconnected-(U8-2A-Pad3)") (class "Default")
      (node (ref "U8") (pin "3") (pinfunction "2A_3") (pintype "unspecified+no_connect"))
    )
    (net (code "91") (name "unconnected-(U8-2Y-Pad4)") (class "Default")
      (node (ref "U8") (pin "4") (pinfunction "2Y_4") (pintype "unspecified+no_connect"))
    )
    (net (code "92") (name "unconnected-(U8-3A-Pad5)") (class "Default")
      (node (ref "U8") (pin "5") (pinfunction "3A_5") (pintype "unspecified+no_connect"))
    )
    (net (code "93") (name "unconnected-(U8-3Y-Pad6)") (class "Default")
      (node (ref "U8") (pin "6") (pinfunction "3Y_6") (pintype "unspecified+no_connect"))
    )
    (net (code "94") (name "unconnected-(U8-4A-Pad9)") (class "Default")
      (node (ref "U8") (pin "9") (pinfunction "4A_9") (pintype "unspecified+no_connect"))
    )
    (net (code "95") (name "unconnected-(U8-4Y-Pad8)") (class "Default")
      (node (ref "U8") (pin "8") (pinfunction "4Y_8") (pintype "unspecified+no_connect"))
    )
    (net (code "96") (name "unconnected-(U8-6A-Pad13)") (class "Default")
      (node (ref "U8") (pin "13") (pinfunction "6A_13") (pintype "unspecified+no_connect"))
    )
    (net (code "97") (name "unconnected-(U8-6Y-Pad12)") (class "Default")
      (node (ref "U8") (pin "12") (pinfunction "6Y_12") (pintype "unspecified+no_connect"))
    )
    (net (code "98") (name "unconnected-(U12-2B-Pad2)") (class "Default")
      (node (ref "U12") (pin "2") (pinfunction "2B_2") (pintype "unspecified+no_connect"))
    )
    (net (code "99") (name "unconnected-(U12-2C-Pad15)") (class "Default")
      (node (ref "U12") (pin "15") (pinfunction "2C_15") (pintype "unspecified+no_connect"))
    )
    (net (code "100") (name "unconnected-(U12-3B-Pad3)") (class "Default")
      (node (ref "U12") (pin "3") (pinfunction "3B_3") (pintype "unspecified+no_connect"))
    )
    (net (code "101") (name "unconnected-(U12-3C-Pad14)") (class "Default")
      (node (ref "U12") (pin "14") (pinfunction "3C_14") (pintype "unspecified+no_connect"))
    )
    (net (code "102") (name "unconnected-(U12-4B-Pad4)") (class "Default")
      (node (ref "U12") (pin "4") (pinfunction "4B_4") (pintype "unspecified+no_connect"))
    )
    (net (code "103") (name "unconnected-(U12-4C-Pad13)") (class "Default")
      (node (ref "U12") (pin "13") (pinfunction "4C_13") (pintype "unspecified+no_connect"))
    )
    (net (code "104") (name "unconnected-(U12-6B-Pad6)") (class "Default")
      (node (ref "U12") (pin "6") (pinfunction "6B_6") (pintype "unspecified+no_connect"))
    )
    (net (code "105") (name "unconnected-(U12-6C-Pad11)") (class "Default")
      (node (ref "U12") (pin "11") (pinfunction "6C_11") (pintype "unspecified+no_connect"))
    )
    (net (code "106") (name "unconnected-(U12-7B-Pad7)") (class "Default")
      (node (ref "U12") (pin "7") (pinfunction "7B_7") (pintype "unspecified+no_connect"))
    )
    (net (code "107") (name "unconnected-(U12-7C-Pad10)") (class "Default")
      (node (ref "U12") (pin "10") (pinfunction "7C_10") (pintype "unspecified+no_connect"))
    )
    (net (code "108") (name "unconnected-(U12-COM-Pad9)") (class "Default")
      (node (ref "U12") (pin "9") (pinfunction "COM_9") (pintype "unspecified+no_connect"))
    )
    (net (code "109") (name "unconnected-(USB1-D+-Pad3)") (class "Default")
      (node (ref "USB1") (pin "3") (pinfunction "D+_3") (pintype "unspecified+no_connect"))
    )
    (net (code "110") (name "unconnected-(USB1-D--Pad2)") (class "Default")
      (node (ref "USB1") (pin "2") (pinfunction "D-_2") (pintype "unspecified+no_connect"))
    )
    (net (code "111") (name "unconnected-(USB1-ID-Pad4)") (class "Default")
      (node (ref "USB1") (pin "4") (pinfunction "ID_4") (pintype "unspecified+no_connect"))
    )
  )
)
